# top.net
KiCad netlist of a schematic drawn in Altium Designer
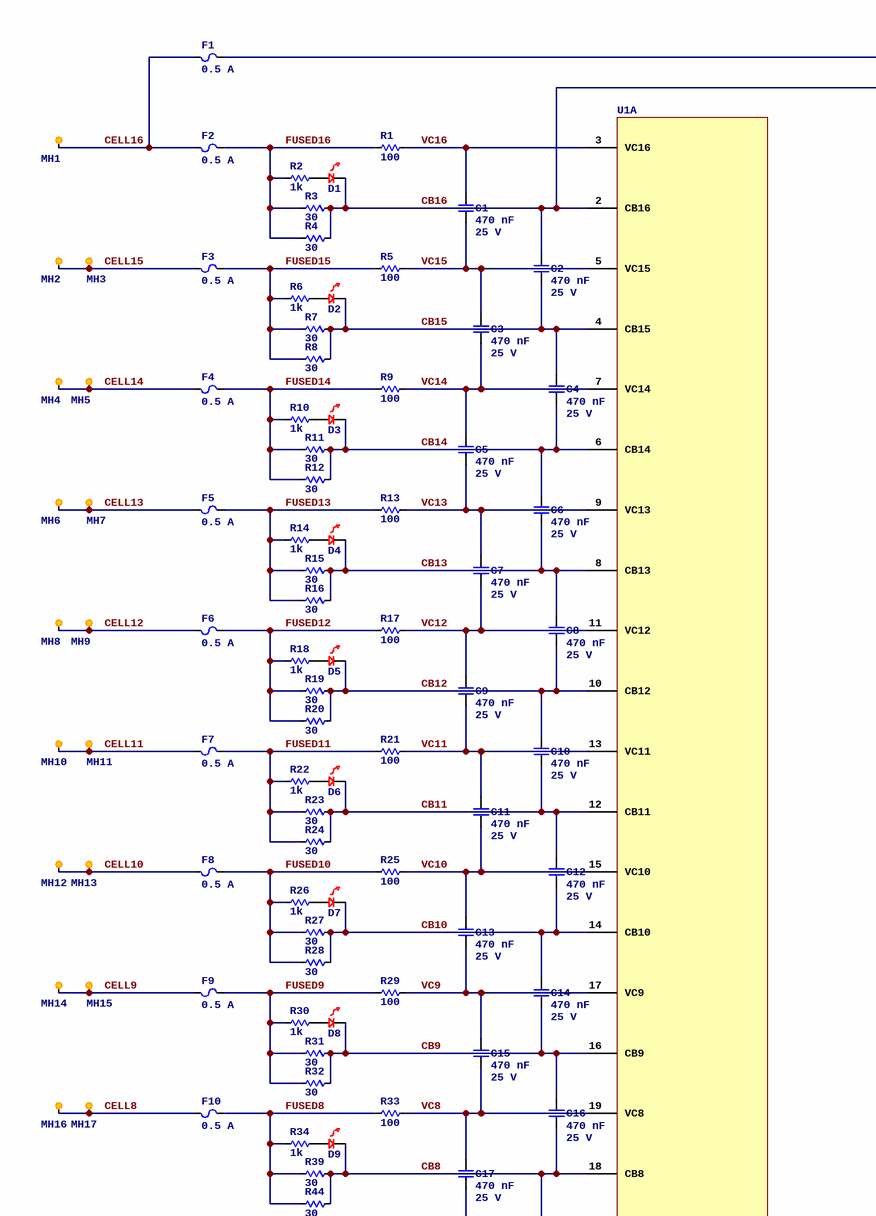
[diagram p0: top.SchDoc, top left]
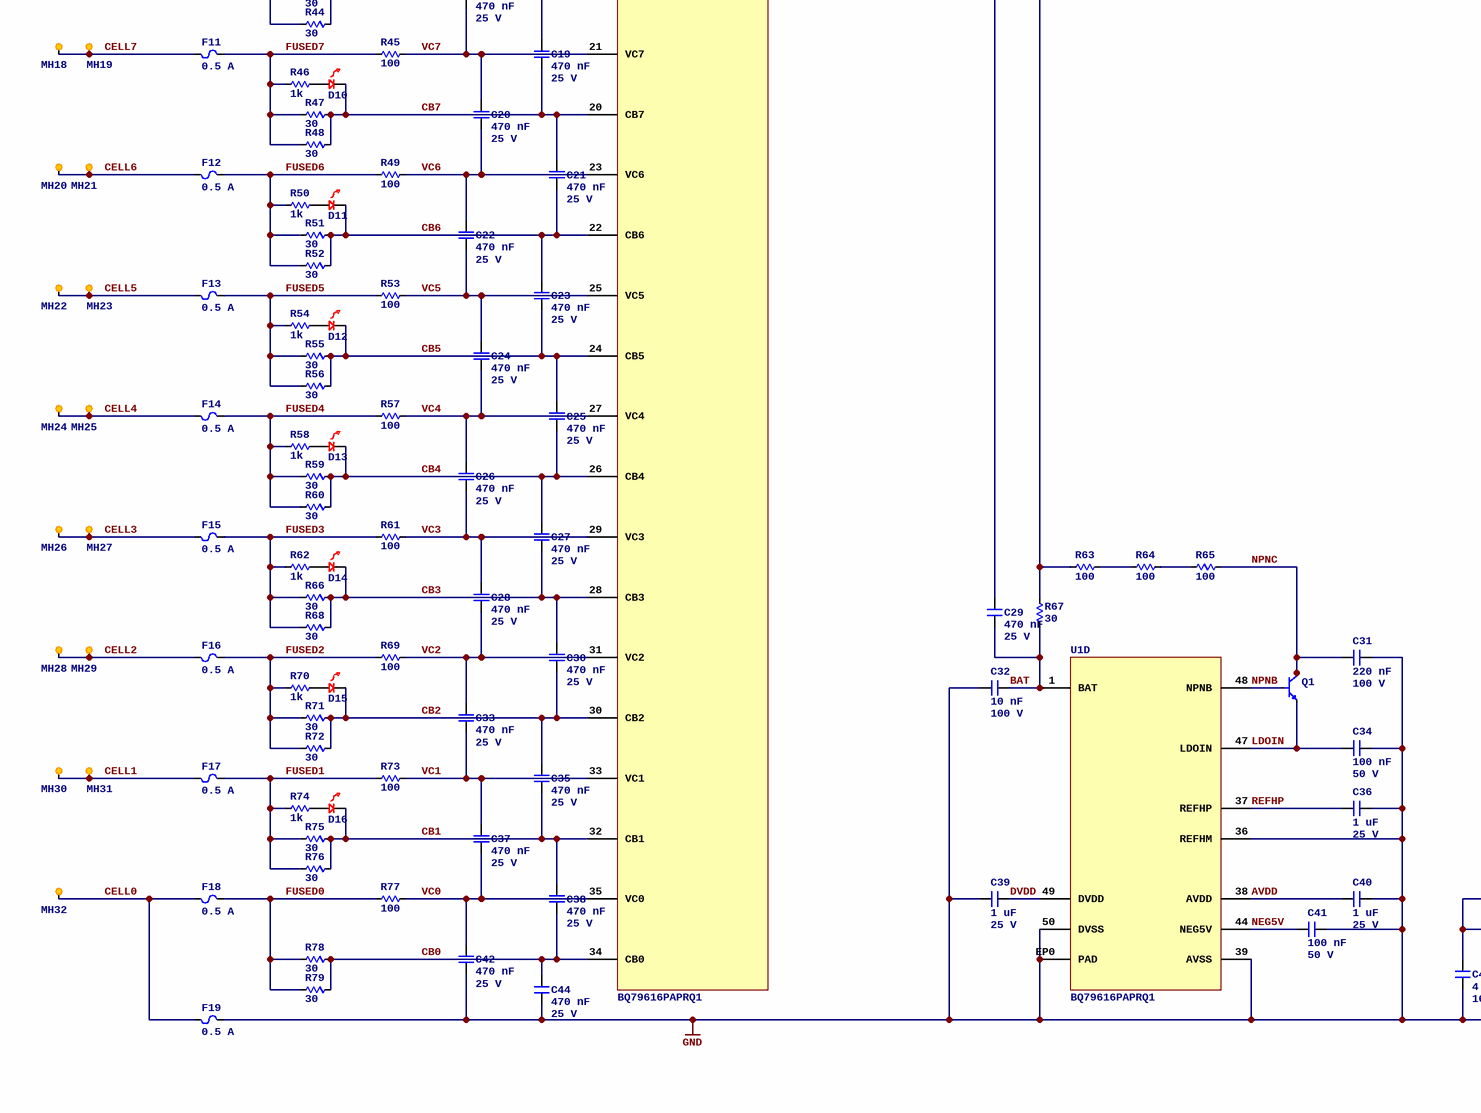
[diagram p1: top.SchDoc, bottom left]
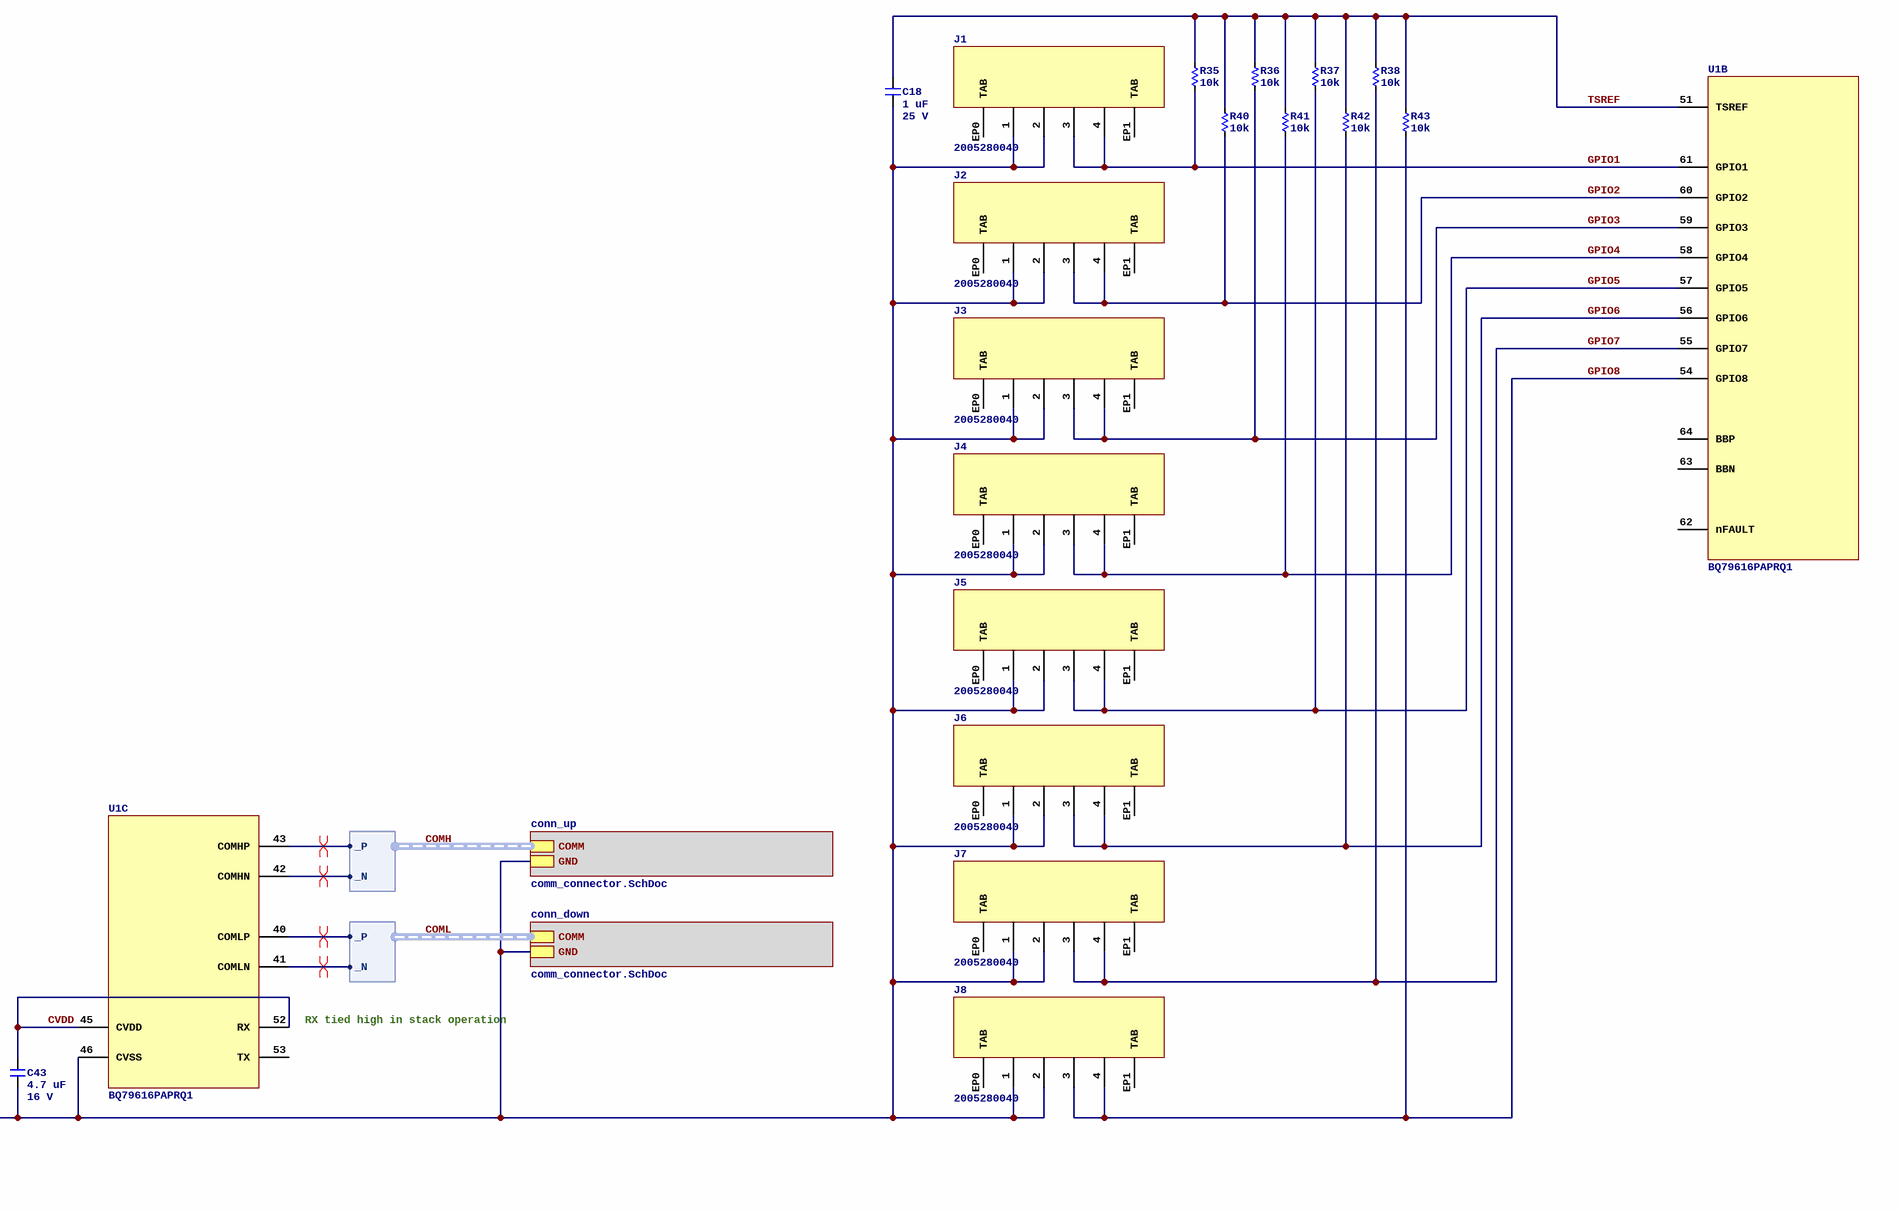
[diagram p2: top.SchDoc, bottom right]

(export (version "E")
  (design (tool "Eeschema 10.0.6"))
  (components
    (comp (ref "C1")
      (value "CL10B474KA8NNNC")
      (footprint "C0603")
      (fields
        (field (name "CAPACITANCE") "470 nF")
        (field (name "MANUFACTURER") "Samsung Electro-Mechanics")
        (field (name "VOLTAGE RATING") "25 V")
      )
      (libsource (lib "database") (part "__template_cap"))
    )
    (comp (ref "C2")
      (value "CL10B474KA8NNNC")
      (footprint "C0603")
      (fields
        (field (name "CAPACITANCE") "470 nF")
        (field (name "MANUFACTURER") "Samsung Electro-Mechanics")
        (field (name "VOLTAGE RATING") "25 V")
      )
      (libsource (lib "database") (part "__template_cap"))
    )
    (comp (ref "C3")
      (value "CL10B474KA8NNNC")
      (footprint "C0603")
      (fields
        (field (name "CAPACITANCE") "470 nF")
        (field (name "MANUFACTURER") "Samsung Electro-Mechanics")
        (field (name "VOLTAGE RATING") "25 V")
      )
      (libsource (lib "database") (part "__template_cap"))
    )
    (comp (ref "C4")
      (value "CL10B474KA8NNNC")
      (footprint "C0603")
      (fields
        (field (name "CAPACITANCE") "470 nF")
        (field (name "MANUFACTURER") "Samsung Electro-Mechanics")
        (field (name "VOLTAGE RATING") "25 V")
      )
      (libsource (lib "database") (part "__template_cap"))
    )
    (comp (ref "C5")
      (value "CL10B474KA8NNNC")
      (footprint "C0603")
      (fields
        (field (name "CAPACITANCE") "470 nF")
        (field (name "MANUFACTURER") "Samsung Electro-Mechanics")
        (field (name "VOLTAGE RATING") "25 V")
      )
      (libsource (lib "database") (part "__template_cap"))
    )
    (comp (ref "C6")
      (value "CL10B474KA8NNNC")
      (footprint "C0603")
      (fields
        (field (name "CAPACITANCE") "470 nF")
        (field (name "MANUFACTURER") "Samsung Electro-Mechanics")
        (field (name "VOLTAGE RATING") "25 V")
      )
      (libsource (lib "database") (part "__template_cap"))
    )
    (comp (ref "C7")
      (value "CL10B474KA8NNNC")
      (footprint "C0603")
      (fields
        (field (name "CAPACITANCE") "470 nF")
        (field (name "MANUFACTURER") "Samsung Electro-Mechanics")
        (field (name "VOLTAGE RATING") "25 V")
      )
      (libsource (lib "database") (part "__template_cap"))
    )
    (comp (ref "C8")
      (value "CL10B474KA8NNNC")
      (footprint "C0603")
      (fields
        (field (name "CAPACITANCE") "470 nF")
        (field (name "MANUFACTURER") "Samsung Electro-Mechanics")
        (field (name "VOLTAGE RATING") "25 V")
      )
      (libsource (lib "database") (part "__template_cap"))
    )
    (comp (ref "C9")
      (value "CL10B474KA8NNNC")
      (footprint "C0603")
      (fields
        (field (name "CAPACITANCE") "470 nF")
        (field (name "MANUFACTURER") "Samsung Electro-Mechanics")
        (field (name "VOLTAGE RATING") "25 V")
      )
      (libsource (lib "database") (part "__template_cap"))
    )
    (comp (ref "C10")
      (value "CL10B474KA8NNNC")
      (footprint "C0603")
      (fields
        (field (name "CAPACITANCE") "470 nF")
        (field (name "MANUFACTURER") "Samsung Electro-Mechanics")
        (field (name "VOLTAGE RATING") "25 V")
      )
      (libsource (lib "database") (part "__template_cap"))
    )
    (comp (ref "C11")
      (value "CL10B474KA8NNNC")
      (footprint "C0603")
      (fields
        (field (name "CAPACITANCE") "470 nF")
        (field (name "MANUFACTURER") "Samsung Electro-Mechanics")
        (field (name "VOLTAGE RATING") "25 V")
      )
      (libsource (lib "database") (part "__template_cap"))
    )
    (comp (ref "C12")
      (value "CL10B474KA8NNNC")
      (footprint "C0603")
      (fields
        (field (name "CAPACITANCE") "470 nF")
        (field (name "MANUFACTURER") "Samsung Electro-Mechanics")
        (field (name "VOLTAGE RATING") "25 V")
      )
      (libsource (lib "database") (part "__template_cap"))
    )
    (comp (ref "C13")
      (value "CL10B474KA8NNNC")
      (footprint "C0603")
      (fields
        (field (name "CAPACITANCE") "470 nF")
        (field (name "MANUFACTURER") "Samsung Electro-Mechanics")
        (field (name "VOLTAGE RATING") "25 V")
      )
      (libsource (lib "database") (part "__template_cap"))
    )
    (comp (ref "C14")
      (value "CL10B474KA8NNNC")
      (footprint "C0603")
      (fields
        (field (name "CAPACITANCE") "470 nF")
        (field (name "MANUFACTURER") "Samsung Electro-Mechanics")
        (field (name "VOLTAGE RATING") "25 V")
      )
      (libsource (lib "database") (part "__template_cap"))
    )
    (comp (ref "C15")
      (value "CL10B474KA8NNNC")
      (footprint "C0603")
      (fields
        (field (name "CAPACITANCE") "470 nF")
        (field (name "MANUFACTURER") "Samsung Electro-Mechanics")
        (field (name "VOLTAGE RATING") "25 V")
      )
      (libsource (lib "database") (part "__template_cap"))
    )
    (comp (ref "C16")
      (value "CL10B474KA8NNNC")
      (footprint "C0603")
      (fields
        (field (name "CAPACITANCE") "470 nF")
        (field (name "MANUFACTURER") "Samsung Electro-Mechanics")
        (field (name "VOLTAGE RATING") "25 V")
      )
      (libsource (lib "database") (part "__template_cap"))
    )
    (comp (ref "C17")
      (value "CL10B474KA8NNNC")
      (footprint "C0603")
      (fields
        (field (name "CAPACITANCE") "470 nF")
        (field (name "MANUFACTURER") "Samsung Electro-Mechanics")
        (field (name "VOLTAGE RATING") "25 V")
      )
      (libsource (lib "database") (part "__template_cap"))
    )
    (comp (ref "C18")
      (value "CL10B105KA8NNNC")
      (footprint "C0603")
      (fields
        (field (name "CAPACITANCE") "1 uF")
        (field (name "MANUFACTURER") "Samsung Electro-Mechanics")
        (field (name "VOLTAGE RATING") "25 V")
      )
      (libsource (lib "database") (part "__template_cap"))
    )
    (comp (ref "C19")
      (value "CL10B474KA8NNNC")
      (footprint "C0603")
      (fields
        (field (name "CAPACITANCE") "470 nF")
        (field (name "MANUFACTURER") "Samsung Electro-Mechanics")
        (field (name "VOLTAGE RATING") "25 V")
      )
      (libsource (lib "database") (part "__template_cap"))
    )
    (comp (ref "C20")
      (value "CL10B474KA8NNNC")
      (footprint "C0603")
      (fields
        (field (name "CAPACITANCE") "470 nF")
        (field (name "MANUFACTURER") "Samsung Electro-Mechanics")
        (field (name "VOLTAGE RATING") "25 V")
      )
      (libsource (lib "database") (part "__template_cap"))
    )
    (comp (ref "C21")
      (value "CL10B474KA8NNNC")
      (footprint "C0603")
      (fields
        (field (name "CAPACITANCE") "470 nF")
        (field (name "MANUFACTURER") "Samsung Electro-Mechanics")
        (field (name "VOLTAGE RATING") "25 V")
      )
      (libsource (lib "database") (part "__template_cap"))
    )
    (comp (ref "C22")
      (value "CL10B474KA8NNNC")
      (footprint "C0603")
      (fields
        (field (name "CAPACITANCE") "470 nF")
        (field (name "MANUFACTURER") "Samsung Electro-Mechanics")
        (field (name "VOLTAGE RATING") "25 V")
      )
      (libsource (lib "database") (part "__template_cap"))
    )
    (comp (ref "C23")
      (value "CL10B474KA8NNNC")
      (footprint "C0603")
      (fields
        (field (name "CAPACITANCE") "470 nF")
        (field (name "MANUFACTURER") "Samsung Electro-Mechanics")
        (field (name "VOLTAGE RATING") "25 V")
      )
      (libsource (lib "database") (part "__template_cap"))
    )
    (comp (ref "C24")
      (value "CL10B474KA8NNNC")
      (footprint "C0603")
      (fields
        (field (name "CAPACITANCE") "470 nF")
        (field (name "MANUFACTURER") "Samsung Electro-Mechanics")
        (field (name "VOLTAGE RATING") "25 V")
      )
      (libsource (lib "database") (part "__template_cap"))
    )
    (comp (ref "C25")
      (value "CL10B474KA8NNNC")
      (footprint "C0603")
      (fields
        (field (name "CAPACITANCE") "470 nF")
        (field (name "MANUFACTURER") "Samsung Electro-Mechanics")
        (field (name "VOLTAGE RATING") "25 V")
      )
      (libsource (lib "database") (part "__template_cap"))
    )
    (comp (ref "C26")
      (value "CL10B474KA8NNNC")
      (footprint "C0603")
      (fields
        (field (name "CAPACITANCE") "470 nF")
        (field (name "MANUFACTURER") "Samsung Electro-Mechanics")
        (field (name "VOLTAGE RATING") "25 V")
      )
      (libsource (lib "database") (part "__template_cap"))
    )
    (comp (ref "C27")
      (value "CL10B474KA8NNNC")
      (footprint "C0603")
      (fields
        (field (name "CAPACITANCE") "470 nF")
        (field (name "MANUFACTURER") "Samsung Electro-Mechanics")
        (field (name "VOLTAGE RATING") "25 V")
      )
      (libsource (lib "database") (part "__template_cap"))
    )
    (comp (ref "C28")
      (value "CL10B474KA8NNNC")
      (footprint "C0603")
      (fields
        (field (name "CAPACITANCE") "470 nF")
        (field (name "MANUFACTURER") "Samsung Electro-Mechanics")
        (field (name "VOLTAGE RATING") "25 V")
      )
      (libsource (lib "database") (part "__template_cap"))
    )
    (comp (ref "C29")
      (value "CL10B474KA8NNNC")
      (footprint "C0603")
      (fields
        (field (name "CAPACITANCE") "470 nF")
        (field (name "MANUFACTURER") "Samsung Electro-Mechanics")
        (field (name "VOLTAGE RATING") "25 V")
      )
      (libsource (lib "database") (part "__template_cap"))
    )
    (comp (ref "C30")
      (value "CL10B474KA8NNNC")
      (footprint "C0603")
      (fields
        (field (name "CAPACITANCE") "470 nF")
        (field (name "MANUFACTURER") "Samsung Electro-Mechanics")
        (field (name "VOLTAGE RATING") "25 V")
      )
      (libsource (lib "database") (part "__template_cap"))
    )
    (comp (ref "C31")
      (value "TCC1206X7R224K101FT")
      (footprint "C1206")
      (fields
        (field (name "CAPACITANCE") "220 nF")
        (field (name "MANUFACTURER") "CCTC")
        (field (name "VOLTAGE RATING") "100 V")
      )
      (libsource (lib "database") (part "__template_cap"))
    )
    (comp (ref "C32")
      (value "CC0402KRX7R0BB103")
      (footprint "C0402")
      (fields
        (field (name "CAPACITANCE") "10 nF")
        (field (name "MANUFACTURER") "YAGEO")
        (field (name "VOLTAGE RATING") "100 V")
      )
      (libsource (lib "database") (part "__template_cap"))
    )
    (comp (ref "C33")
      (value "CL10B474KA8NNNC")
      (footprint "C0603")
      (fields
        (field (name "CAPACITANCE") "470 nF")
        (field (name "MANUFACTURER") "Samsung Electro-Mechanics")
        (field (name "VOLTAGE RATING") "25 V")
      )
      (libsource (lib "database") (part "__template_cap"))
    )
    (comp (ref "C34")
      (value "CL05B104KB54PNC")
      (footprint "C0402")
      (fields
        (field (name "CAPACITANCE") "100 nF")
        (field (name "MANUFACTURER") "Samsung Electro-Mechanics")
        (field (name "VOLTAGE RATING") "50 V")
      )
      (libsource (lib "database") (part "__template_cap"))
    )
    (comp (ref "C35")
      (value "CL10B474KA8NNNC")
      (footprint "C0603")
      (fields
        (field (name "CAPACITANCE") "470 nF")
        (field (name "MANUFACTURER") "Samsung Electro-Mechanics")
        (field (name "VOLTAGE RATING") "25 V")
      )
      (libsource (lib "database") (part "__template_cap"))
    )
    (comp (ref "C36")
      (value "CL10B105KA8NNNC")
      (footprint "C0603")
      (fields
        (field (name "CAPACITANCE") "1 uF")
        (field (name "MANUFACTURER") "Samsung Electro-Mechanics")
        (field (name "VOLTAGE RATING") "25 V")
      )
      (libsource (lib "database") (part "__template_cap"))
    )
    (comp (ref "C37")
      (value "CL10B474KA8NNNC")
      (footprint "C0603")
      (fields
        (field (name "CAPACITANCE") "470 nF")
        (field (name "MANUFACTURER") "Samsung Electro-Mechanics")
        (field (name "VOLTAGE RATING") "25 V")
      )
      (libsource (lib "database") (part "__template_cap"))
    )
    (comp (ref "C38")
      (value "CL10B474KA8NNNC")
      (footprint "C0603")
      (fields
        (field (name "CAPACITANCE") "470 nF")
        (field (name "MANUFACTURER") "Samsung Electro-Mechanics")
        (field (name "VOLTAGE RATING") "25 V")
      )
      (libsource (lib "database") (part "__template_cap"))
    )
    (comp (ref "C39")
      (value "CL10B105KA8NNNC")
      (footprint "C0603")
      (fields
        (field (name "CAPACITANCE") "1 uF")
        (field (name "MANUFACTURER") "Samsung Electro-Mechanics")
        (field (name "VOLTAGE RATING") "25 V")
      )
      (libsource (lib "database") (part "__template_cap"))
    )
    (comp (ref "C40")
      (value "CL10B105KA8NNNC")
      (footprint "C0603")
      (fields
        (field (name "CAPACITANCE") "1 uF")
        (field (name "MANUFACTURER") "Samsung Electro-Mechanics")
        (field (name "VOLTAGE RATING") "25 V")
      )
      (libsource (lib "database") (part "__template_cap"))
    )
    (comp (ref "C41")
      (value "CL05B104KB54PNC")
      (footprint "C0402")
      (fields
        (field (name "CAPACITANCE") "100 nF")
        (field (name "MANUFACTURER") "Samsung Electro-Mechanics")
        (field (name "VOLTAGE RATING") "50 V")
      )
      (libsource (lib "database") (part "__template_cap"))
    )
    (comp (ref "C42")
      (value "CL10B474KA8NNNC")
      (footprint "C0603")
      (fields
        (field (name "CAPACITANCE") "470 nF")
        (field (name "MANUFACTURER") "Samsung Electro-Mechanics")
        (field (name "VOLTAGE RATING") "25 V")
      )
      (libsource (lib "database") (part "__template_cap"))
    )
    (comp (ref "C43")
      (value "CL21B475KOFNNNE")
      (footprint "C0805")
      (fields
        (field (name "CAPACITANCE") "4.7 uF")
        (field (name "MANUFACTURER") "Samsung Electro-Mechanics")
        (field (name "VOLTAGE RATING") "16 V")
      )
      (libsource (lib "database") (part "__template_cap"))
    )
    (comp (ref "C44")
      (value "CL10B474KA8NNNC")
      (footprint "C0603")
      (fields
        (field (name "CAPACITANCE") "470 nF")
        (field (name "MANUFACTURER") "Samsung Electro-Mechanics")
        (field (name "VOLTAGE RATING") "25 V")
      )
      (libsource (lib "database") (part "__template_cap"))
    )
    (comp (ref "D1")
      (value "LTST-C190KRKT")
      (footprint "LED_0603P_RED")
      (description "LED SUPER RED CLEAR 0603 SMD")
      (fields (field (name "MANUFACTURER") "Lite-On Inc"))
      (libsource (lib "database") (part "__template_led_red"))
    )
    (comp (ref "D2")
      (value "LTST-C190KRKT")
      (footprint "LED_0603P_RED")
      (description "LED SUPER RED CLEAR 0603 SMD")
      (fields (field (name "MANUFACTURER") "Lite-On Inc"))
      (libsource (lib "database") (part "__template_led_red"))
    )
    (comp (ref "D3")
      (value "LTST-C190KRKT")
      (footprint "LED_0603P_RED")
      (description "LED SUPER RED CLEAR 0603 SMD")
      (fields (field (name "MANUFACTURER") "Lite-On Inc"))
      (libsource (lib "database") (part "__template_led_red"))
    )
    (comp (ref "D4")
      (value "LTST-C190KRKT")
      (footprint "LED_0603P_RED")
      (description "LED SUPER RED CLEAR 0603 SMD")
      (fields (field (name "MANUFACTURER") "Lite-On Inc"))
      (libsource (lib "database") (part "__template_led_red"))
    )
    (comp (ref "D5")
      (value "LTST-C190KRKT")
      (footprint "LED_0603P_RED")
      (description "LED SUPER RED CLEAR 0603 SMD")
      (fields (field (name "MANUFACTURER") "Lite-On Inc"))
      (libsource (lib "database") (part "__template_led_red"))
    )
    (comp (ref "D6")
      (value "LTST-C190KRKT")
      (footprint "LED_0603P_RED")
      (description "LED SUPER RED CLEAR 0603 SMD")
      (fields (field (name "MANUFACTURER") "Lite-On Inc"))
      (libsource (lib "database") (part "__template_led_red"))
    )
    (comp (ref "D7")
      (value "LTST-C190KRKT")
      (footprint "LED_0603P_RED")
      (description "LED SUPER RED CLEAR 0603 SMD")
      (fields (field (name "MANUFACTURER") "Lite-On Inc"))
      (libsource (lib "database") (part "__template_led_red"))
    )
    (comp (ref "D8")
      (value "LTST-C190KRKT")
      (footprint "LED_0603P_RED")
      (description "LED SUPER RED CLEAR 0603 SMD")
      (fields (field (name "MANUFACTURER") "Lite-On Inc"))
      (libsource (lib "database") (part "__template_led_red"))
    )
    (comp (ref "D9")
      (value "LTST-C190KRKT")
      (footprint "LED_0603P_RED")
      (description "LED SUPER RED CLEAR 0603 SMD")
      (fields (field (name "MANUFACTURER") "Lite-On Inc"))
      (libsource (lib "database") (part "__template_led_red"))
    )
    (comp (ref "D10")
      (value "LTST-C190KRKT")
      (footprint "LED_0603P_RED")
      (description "LED SUPER RED CLEAR 0603 SMD")
      (fields (field (name "MANUFACTURER") "Lite-On Inc"))
      (libsource (lib "database") (part "__template_led_red"))
    )
    (comp (ref "D11")
      (value "LTST-C190KRKT")
      (footprint "LED_0603P_RED")
      (description "LED SUPER RED CLEAR 0603 SMD")
      (fields (field (name "MANUFACTURER") "Lite-On Inc"))
      (libsource (lib "database") (part "__template_led_red"))
    )
    (comp (ref "D12")
      (value "LTST-C190KRKT")
      (footprint "LED_0603P_RED")
      (description "LED SUPER RED CLEAR 0603 SMD")
      (fields (field (name "MANUFACTURER") "Lite-On Inc"))
      (libsource (lib "database") (part "__template_led_red"))
    )
    (comp (ref "D13")
      (value "LTST-C190KRKT")
      (footprint "LED_0603P_RED")
      (description "LED SUPER RED CLEAR 0603 SMD")
      (fields (field (name "MANUFACTURER") "Lite-On Inc"))
      (libsource (lib "database") (part "__template_led_red"))
    )
    (comp (ref "D14")
      (value "LTST-C190KRKT")
      (footprint "LED_0603P_RED")
      (description "LED SUPER RED CLEAR 0603 SMD")
      (fields (field (name "MANUFACTURER") "Lite-On Inc"))
      (libsource (lib "database") (part "__template_led_red"))
    )
    (comp (ref "D15")
      (value "LTST-C190KRKT")
      (footprint "LED_0603P_RED")
      (description "LED SUPER RED CLEAR 0603 SMD")
      (fields (field (name "MANUFACTURER") "Lite-On Inc"))
      (libsource (lib "database") (part "__template_led_red"))
    )
    (comp (ref "D16")
      (value "LTST-C190KRKT")
      (footprint "LED_0603P_RED")
      (description "LED SUPER RED CLEAR 0603 SMD")
      (fields (field (name "MANUFACTURER") "Lite-On Inc"))
      (libsource (lib "database") (part "__template_led_red"))
    )
    (comp (ref "F1")
      (value "JFC2410-0500TS")
      (footprint "JDTFUSE_JFC2410")
      (description "FUSE 0.5A 250V SMD")
      (fields (field (name "MANUFACTURER") "Shenzhen JDTfuse") (field (name "CURRENT") "0.5 A"))
      (libsource (lib "database") (part "JFC2410-0500TS"))
    )
    (comp (ref "F2")
      (value "JFC2410-0500TS")
      (footprint "JDTFUSE_JFC2410")
      (description "FUSE 0.5A 250V SMD")
      (fields (field (name "MANUFACTURER") "Shenzhen JDTfuse") (field (name "CURRENT") "0.5 A"))
      (libsource (lib "database") (part "JFC2410-0500TS"))
    )
    (comp (ref "F3")
      (value "JFC2410-0500TS")
      (footprint "JDTFUSE_JFC2410")
      (description "FUSE 0.5A 250V SMD")
      (fields (field (name "MANUFACTURER") "Shenzhen JDTfuse") (field (name "CURRENT") "0.5 A"))
      (libsource (lib "database") (part "JFC2410-0500TS"))
    )
    (comp (ref "F4")
      (value "JFC2410-0500TS")
      (footprint "JDTFUSE_JFC2410")
      (description "FUSE 0.5A 250V SMD")
      (fields (field (name "MANUFACTURER") "Shenzhen JDTfuse") (field (name "CURRENT") "0.5 A"))
      (libsource (lib "database") (part "JFC2410-0500TS"))
    )
    (comp (ref "F5")
      (value "JFC2410-0500TS")
      (footprint "JDTFUSE_JFC2410")
      (description "FUSE 0.5A 250V SMD")
      (fields (field (name "MANUFACTURER") "Shenzhen JDTfuse") (field (name "CURRENT") "0.5 A"))
      (libsource (lib "database") (part "JFC2410-0500TS"))
    )
    (comp (ref "F6")
      (value "JFC2410-0500TS")
      (footprint "JDTFUSE_JFC2410")
      (description "FUSE 0.5A 250V SMD")
      (fields (field (name "MANUFACTURER") "Shenzhen JDTfuse") (field (name "CURRENT") "0.5 A"))
      (libsource (lib "database") (part "JFC2410-0500TS"))
    )
    (comp (ref "F7")
      (value "JFC2410-0500TS")
      (footprint "JDTFUSE_JFC2410")
      (description "FUSE 0.5A 250V SMD")
      (fields (field (name "MANUFACTURER") "Shenzhen JDTfuse") (field (name "CURRENT") "0.5 A"))
      (libsource (lib "database") (part "JFC2410-0500TS"))
    )
    (comp (ref "F8")
      (value "JFC2410-0500TS")
      (footprint "JDTFUSE_JFC2410")
      (description "FUSE 0.5A 250V SMD")
      (fields (field (name "MANUFACTURER") "Shenzhen JDTfuse") (field (name "CURRENT") "0.5 A"))
      (libsource (lib "database") (part "JFC2410-0500TS"))
    )
    (comp (ref "F9")
      (value "JFC2410-0500TS")
      (footprint "JDTFUSE_JFC2410")
      (description "FUSE 0.5A 250V SMD")
      (fields (field (name "MANUFACTURER") "Shenzhen JDTfuse") (field (name "CURRENT") "0.5 A"))
      (libsource (lib "database") (part "JFC2410-0500TS"))
    )
    (comp (ref "F10")
      (value "JFC2410-0500TS")
      (footprint "JDTFUSE_JFC2410")
      (description "FUSE 0.5A 250V SMD")
      (fields (field (name "MANUFACTURER") "Shenzhen JDTfuse") (field (name "CURRENT") "0.5 A"))
      (libsource (lib "database") (part "JFC2410-0500TS"))
    )
    (comp (ref "F11")
      (value "JFC2410-0500TS")
      (footprint "JDTFUSE_JFC2410")
      (description "FUSE 0.5A 250V SMD")
      (fields (field (name "MANUFACTURER") "Shenzhen JDTfuse") (field (name "CURRENT") "0.5 A"))
      (libsource (lib "database") (part "JFC2410-0500TS"))
    )
    (comp (ref "F12")
      (value "JFC2410-0500TS")
      (footprint "JDTFUSE_JFC2410")
      (description "FUSE 0.5A 250V SMD")
      (fields (field (name "MANUFACTURER") "Shenzhen JDTfuse") (field (name "CURRENT") "0.5 A"))
      (libsource (lib "database") (part "JFC2410-0500TS"))
    )
    (comp (ref "F13")
      (value "JFC2410-0500TS")
      (footprint "JDTFUSE_JFC2410")
      (description "FUSE 0.5A 250V SMD")
      (fields (field (name "MANUFACTURER") "Shenzhen JDTfuse") (field (name "CURRENT") "0.5 A"))
      (libsource (lib "database") (part "JFC2410-0500TS"))
    )
    (comp (ref "F14")
      (value "JFC2410-0500TS")
      (footprint "JDTFUSE_JFC2410")
      (description "FUSE 0.5A 250V SMD")
      (fields (field (name "MANUFACTURER") "Shenzhen JDTfuse") (field (name "CURRENT") "0.5 A"))
      (libsource (lib "database") (part "JFC2410-0500TS"))
    )
    (comp (ref "F15")
      (value "JFC2410-0500TS")
      (footprint "JDTFUSE_JFC2410")
      (description "FUSE 0.5A 250V SMD")
      (fields (field (name "MANUFACTURER") "Shenzhen JDTfuse") (field (name "CURRENT") "0.5 A"))
      (libsource (lib "database") (part "JFC2410-0500TS"))
    )
    (comp (ref "F16")
      (value "JFC2410-0500TS")
      (footprint "JDTFUSE_JFC2410")
      (description "FUSE 0.5A 250V SMD")
      (fields (field (name "MANUFACTURER") "Shenzhen JDTfuse") (field (name "CURRENT") "0.5 A"))
      (libsource (lib "database") (part "JFC2410-0500TS"))
    )
    (comp (ref "F17")
      (value "JFC2410-0500TS")
      (footprint "JDTFUSE_JFC2410")
      (description "FUSE 0.5A 250V SMD")
      (fields (field (name "MANUFACTURER") "Shenzhen JDTfuse") (field (name "CURRENT") "0.5 A"))
      (libsource (lib "database") (part "JFC2410-0500TS"))
    )
    (comp (ref "F18")
      (value "JFC2410-0500TS")
      (footprint "JDTFUSE_JFC2410")
      (description "FUSE 0.5A 250V SMD")
      (fields (field (name "MANUFACTURER") "Shenzhen JDTfuse") (field (name "CURRENT") "0.5 A"))
      (libsource (lib "database") (part "JFC2410-0500TS"))
    )
    (comp (ref "F19")
      (value "JFC2410-0500TS")
      (footprint "JDTFUSE_JFC2410")
      (description "FUSE 0.5A 250V SMD")
      (fields (field (name "MANUFACTURER") "Shenzhen JDTfuse") (field (name "CURRENT") "0.5 A"))
      (libsource (lib "database") (part "JFC2410-0500TS"))
    )
    (comp (ref "J1")
      (value "2005280040")
      (footprint "MOLEX_FD19_1.00mm_2005280040")
      (description "4 Position FFC, FPC Connector Contacts, Bottom 0.039\" (1.00mm) Surface Mount, Right Angle")
      (fields (field (name "MANUFACTURER") "Molex"))
      (libsource (lib "database") (part "2005280040"))
    )
    (comp (ref "J2")
      (value "2005280040")
      (footprint "MOLEX_FD19_1.00mm_2005280040")
      (description "4 Position FFC, FPC Connector Contacts, Bottom 0.039\" (1.00mm) Surface Mount, Right Angle")
      (fields (field (name "MANUFACTURER") "Molex"))
      (libsource (lib "database") (part "2005280040"))
    )
    (comp (ref "J3")
      (value "2005280040")
      (footprint "MOLEX_FD19_1.00mm_2005280040")
      (description "4 Position FFC, FPC Connector Contacts, Bottom 0.039\" (1.00mm) Surface Mount, Right Angle")
      (fields (field (name "MANUFACTURER") "Molex"))
      (libsource (lib "database") (part "2005280040"))
    )
    (comp (ref "J4")
      (value "2005280040")
      (footprint "MOLEX_FD19_1.00mm_2005280040")
      (description "4 Position FFC, FPC Connector Contacts, Bottom 0.039\" (1.00mm) Surface Mount, Right Angle")
      (fields (field (name "MANUFACTURER") "Molex"))
      (libsource (lib "database") (part "2005280040"))
    )
    (comp (ref "J5")
      (value "2005280040")
      (footprint "MOLEX_FD19_1.00mm_2005280040")
      (description "4 Position FFC, FPC Connector Contacts, Bottom 0.039\" (1.00mm) Surface Mount, Right Angle")
      (fields (field (name "MANUFACTURER") "Molex"))
      (libsource (lib "database") (part "2005280040"))
    )
    (comp (ref "J6")
      (value "2005280040")
      (footprint "MOLEX_FD19_1.00mm_2005280040")
      (description "4 Position FFC, FPC Connector Contacts, Bottom 0.039\" (1.00mm) Surface Mount, Right Angle")
      (fields (field (name "MANUFACTURER") "Molex"))
      (libsource (lib "database") (part "2005280040"))
    )
    (comp (ref "J7")
      (value "2005280040")
      (footprint "MOLEX_FD19_1.00mm_2005280040")
      (description "4 Position FFC, FPC Connector Contacts, Bottom 0.039\" (1.00mm) Surface Mount, Right Angle")
      (fields (field (name "MANUFACTURER") "Molex"))
      (libsource (lib "database") (part "2005280040"))
    )
    (comp (ref "J8")
      (value "2005280040")
      (footprint "MOLEX_FD19_1.00mm_2005280040")
      (description "4 Position FFC, FPC Connector Contacts, Bottom 0.039\" (1.00mm) Surface Mount, Right Angle")
      (fields (field (name "MANUFACTURER") "Molex"))
      (libsource (lib "database") (part "2005280040"))
    )
    (comp (ref "MH1") (value "HOLE_M2") (footprint "HOLE_M2") (libsource (lib "database") (part "HOLE")))
    (comp (ref "MH2") (value "HOLE_M2") (footprint "HOLE_M2") (libsource (lib "database") (part "HOLE")))
    (comp (ref "MH3") (value "HOLE_M2") (footprint "HOLE_M2") (libsource (lib "database") (part "HOLE")))
    (comp (ref "MH4") (value "HOLE_M2") (footprint "HOLE_M2") (libsource (lib "database") (part "HOLE")))
    (comp (ref "MH5") (value "HOLE_M2") (footprint "HOLE_M2") (libsource (lib "database") (part "HOLE")))
    (comp (ref "MH6") (value "HOLE_M2") (footprint "HOLE_M2") (libsource (lib "database") (part "HOLE")))
    (comp (ref "MH7") (value "HOLE_M2") (footprint "HOLE_M2") (libsource (lib "database") (part "HOLE")))
    (comp (ref "MH8") (value "HOLE_M2") (footprint "HOLE_M2") (libsource (lib "database") (part "HOLE")))
    (comp (ref "MH9") (value "HOLE_M2") (footprint "HOLE_M2") (libsource (lib "database") (part "HOLE")))
    (comp (ref "MH10") (value "HOLE_M2") (footprint "HOLE_M2") (libsource (lib "database") (part "HOLE")))
    (comp (ref "MH11") (value "HOLE_M2") (footprint "HOLE_M2") (libsource (lib "database") (part "HOLE")))
    (comp (ref "MH12") (value "HOLE_M2") (footprint "HOLE_M2") (libsource (lib "database") (part "HOLE")))
    (comp (ref "MH13") (value "HOLE_M2") (footprint "HOLE_M2") (libsource (lib "database") (part "HOLE")))
    (comp (ref "MH14") (value "HOLE_M2") (footprint "HOLE_M2") (libsource (lib "database") (part "HOLE")))
    (comp (ref "MH15") (value "HOLE_M2") (footprint "HOLE_M2") (libsource (lib "database") (part "HOLE")))
    (comp (ref "MH16") (value "HOLE_M2") (footprint "HOLE_M2") (libsource (lib "database") (part "HOLE")))
    (comp (ref "MH17") (value "HOLE_M2") (footprint "HOLE_M2") (libsource (lib "database") (part "HOLE")))
    (comp (ref "MH18") (value "HOLE_M2") (footprint "HOLE_M2") (libsource (lib "database") (part "HOLE")))
    (comp (ref "MH19") (value "HOLE_M2") (footprint "HOLE_M2") (libsource (lib "database") (part "HOLE")))
    (comp (ref "MH20") (value "HOLE_M2") (footprint "HOLE_M2") (libsource (lib "database") (part "HOLE")))
    (comp (ref "MH21") (value "HOLE_M2") (footprint "HOLE_M2") (libsource (lib "database") (part "HOLE")))
    (comp (ref "MH22") (value "HOLE_M2") (footprint "HOLE_M2") (libsource (lib "database") (part "HOLE")))
    (comp (ref "MH23") (value "HOLE_M2") (footprint "HOLE_M2") (libsource (lib "database") (part "HOLE")))
    (comp (ref "MH24") (value "HOLE_M2") (footprint "HOLE_M2") (libsource (lib "database") (part "HOLE")))
    (comp (ref "MH25") (value "HOLE_M2") (footprint "HOLE_M2") (libsource (lib "database") (part "HOLE")))
    (comp (ref "MH26") (value "HOLE_M2") (footprint "HOLE_M2") (libsource (lib "database") (part "HOLE")))
    (comp (ref "MH27") (value "HOLE_M2") (footprint "HOLE_M2") (libsource (lib "database") (part "HOLE")))
    (comp (ref "MH28") (value "HOLE_M2") (footprint "HOLE_M2") (libsource (lib "database") (part "HOLE")))
    (comp (ref "MH29") (value "HOLE_M2") (footprint "HOLE_M2") (libsource (lib "database") (part "HOLE")))
    (comp (ref "MH30") (value "HOLE_M2") (footprint "HOLE_M2") (libsource (lib "database") (part "HOLE")))
    (comp (ref "MH31") (value "HOLE_M2") (footprint "HOLE_M2") (libsource (lib "database") (part "HOLE")))
    (comp (ref "MH32") (value "HOLE_M2") (footprint "HOLE_M2") (libsource (lib "database") (part "HOLE")))
    (comp (ref "Q1")
      (value "NSV1C201MZ4T1G")
      (footprint "4SOT223")
      (description "Small Signal Bipolar Transistor, 2A I(C), 100V V(BR)CEO, 1-Element, NPN, Silicon, TO-261AA")
      (fields (field (name "MANUFACTURER") "ON Semiconductor") (field (name "VOLTAGE") "100 V"))
      (libsource (lib "database") (part "NSV1C201MZ4T1G"))
    )
    (comp (ref "R1")
      (value "100")
      (footprint "R0402")
      (fields
        (field (name "MANUFACTURER PART NUMBER") "RC0402FR-07100RL")
        (field (name "MANUFACTURER") "YAGEO")
        (field (name "TOLERANCE") "1%")
      )
      (libsource (lib "database") (part "__template_resistor"))
    )
    (comp (ref "R2")
      (value "1k")
      (footprint "R0402")
      (fields
        (field (name "TOLERANCE") "1%")
        (field (name "MANUFACTURER PART NUMBER") "0402WGF1001TCE")
        (field (name "MANUFACTURER") "UNI-ROYAL(Uniroyal Elec)")
      )
      (libsource (lib "database") (part "__template_resistor"))
    )
    (comp (ref "R3")
      (value "30")
      (footprint "R2512")
      (fields
        (field (name "MANUFACTURER PART NUMBER") "RC2512FK-0730RL")
        (field (name "MANUFACTURER") "YAGEO")
        (field (name "TOLERANCE") "1%")
      )
      (libsource (lib "database") (part "__template_resistor"))
    )
    (comp (ref "R4")
      (value "30")
      (footprint "R2512")
      (fields
        (field (name "MANUFACTURER PART NUMBER") "RC2512FK-0730RL")
        (field (name "MANUFACTURER") "YAGEO")
        (field (name "TOLERANCE") "1%")
      )
      (libsource (lib "database") (part "__template_resistor"))
    )
    (comp (ref "R5")
      (value "100")
      (footprint "R0402")
      (fields
        (field (name "MANUFACTURER PART NUMBER") "RC0402FR-07100RL")
        (field (name "MANUFACTURER") "YAGEO")
        (field (name "TOLERANCE") "1%")
      )
      (libsource (lib "database") (part "__template_resistor"))
    )
    (comp (ref "R6")
      (value "1k")
      (footprint "R0402")
      (fields
        (field (name "TOLERANCE") "1%")
        (field (name "MANUFACTURER PART NUMBER") "0402WGF1001TCE")
        (field (name "MANUFACTURER") "UNI-ROYAL(Uniroyal Elec)")
      )
      (libsource (lib "database") (part "__template_resistor"))
    )
    (comp (ref "R7")
      (value "30")
      (footprint "R2512")
      (fields
        (field (name "MANUFACTURER PART NUMBER") "RC2512FK-0730RL")
        (field (name "MANUFACTURER") "YAGEO")
        (field (name "TOLERANCE") "1%")
      )
      (libsource (lib "database") (part "__template_resistor"))
    )
    (comp (ref "R8")
      (value "30")
      (footprint "R2512")
      (fields
        (field (name "MANUFACTURER PART NUMBER") "RC2512FK-0730RL")
        (field (name "MANUFACTURER") "YAGEO")
        (field (name "TOLERANCE") "1%")
      )
      (libsource (lib "database") (part "__template_resistor"))
    )
    (comp (ref "R9")
      (value "100")
      (footprint "R0402")
      (fields
        (field (name "MANUFACTURER PART NUMBER") "RC0402FR-07100RL")
        (field (name "MANUFACTURER") "YAGEO")
        (field (name "TOLERANCE") "1%")
      )
      (libsource (lib "database") (part "__template_resistor"))
    )
    (comp (ref "R10")
      (value "1k")
      (footprint "R0402")
      (fields
        (field (name "TOLERANCE") "1%")
        (field (name "MANUFACTURER PART NUMBER") "0402WGF1001TCE")
        (field (name "MANUFACTURER") "UNI-ROYAL(Uniroyal Elec)")
      )
      (libsource (lib "database") (part "__template_resistor"))
    )
    (comp (ref "R11")
      (value "30")
      (footprint "R2512")
      (fields
        (field (name "MANUFACTURER PART NUMBER") "RC2512FK-0730RL")
        (field (name "MANUFACTURER") "YAGEO")
        (field (name "TOLERANCE") "1%")
      )
      (libsource (lib "database") (part "__template_resistor"))
    )
    (comp (ref "R12")
      (value "30")
      (footprint "R2512")
      (fields
        (field (name "MANUFACTURER PART NUMBER") "RC2512FK-0730RL")
        (field (name "MANUFACTURER") "YAGEO")
        (field (name "TOLERANCE") "1%")
      )
      (libsource (lib "database") (part "__template_resistor"))
    )
    (comp (ref "R13")
      (value "100")
      (footprint "R0402")
      (fields
        (field (name "MANUFACTURER PART NUMBER") "RC0402FR-07100RL")
        (field (name "MANUFACTURER") "YAGEO")
        (field (name "TOLERANCE") "1%")
      )
      (libsource (lib "database") (part "__template_resistor"))
    )
    (comp (ref "R14")
      (value "1k")
      (footprint "R0402")
      (fields
        (field (name "TOLERANCE") "1%")
        (field (name "MANUFACTURER PART NUMBER") "0402WGF1001TCE")
        (field (name "MANUFACTURER") "UNI-ROYAL(Uniroyal Elec)")
      )
      (libsource (lib "database") (part "__template_resistor"))
    )
    (comp (ref "R15")
      (value "30")
      (footprint "R2512")
      (fields
        (field (name "MANUFACTURER PART NUMBER") "RC2512FK-0730RL")
        (field (name "MANUFACTURER") "YAGEO")
        (field (name "TOLERANCE") "1%")
      )
      (libsource (lib "database") (part "__template_resistor"))
    )
    (comp (ref "R16")
      (value "30")
      (footprint "R2512")
      (fields
        (field (name "MANUFACTURER PART NUMBER") "RC2512FK-0730RL")
        (field (name "MANUFACTURER") "YAGEO")
        (field (name "TOLERANCE") "1%")
      )
      (libsource (lib "database") (part "__template_resistor"))
    )
    (comp (ref "R17")
      (value "100")
      (footprint "R0402")
      (fields
        (field (name "MANUFACTURER PART NUMBER") "RC0402FR-07100RL")
        (field (name "MANUFACTURER") "YAGEO")
        (field (name "TOLERANCE") "1%")
      )
      (libsource (lib "database") (part "__template_resistor"))
    )
    (comp (ref "R18")
      (value "1k")
      (footprint "R0402")
      (fields
        (field (name "TOLERANCE") "1%")
        (field (name "MANUFACTURER PART NUMBER") "0402WGF1001TCE")
        (field (name "MANUFACTURER") "UNI-ROYAL(Uniroyal Elec)")
      )
      (libsource (lib "database") (part "__template_resistor"))
    )
    (comp (ref "R19")
      (value "30")
      (footprint "R2512")
      (fields
        (field (name "MANUFACTURER PART NUMBER") "RC2512FK-0730RL")
        (field (name "MANUFACTURER") "YAGEO")
        (field (name "TOLERANCE") "1%")
      )
      (libsource (lib "database") (part "__template_resistor"))
    )
    (comp (ref "R20")
      (value "30")
      (footprint "R2512")
      (fields
        (field (name "MANUFACTURER PART NUMBER") "RC2512FK-0730RL")
        (field (name "MANUFACTURER") "YAGEO")
        (field (name "TOLERANCE") "1%")
      )
      (libsource (lib "database") (part "__template_resistor"))
    )
    (comp (ref "R21")
      (value "100")
      (footprint "R0402")
      (fields
        (field (name "MANUFACTURER PART NUMBER") "RC0402FR-07100RL")
        (field (name "MANUFACTURER") "YAGEO")
        (field (name "TOLERANCE") "1%")
      )
      (libsource (lib "database") (part "__template_resistor"))
    )
    (comp (ref "R22")
      (value "1k")
      (footprint "R0402")
      (fields
        (field (name "TOLERANCE") "1%")
        (field (name "MANUFACTURER PART NUMBER") "0402WGF1001TCE")
        (field (name "MANUFACTURER") "UNI-ROYAL(Uniroyal Elec)")
      )
      (libsource (lib "database") (part "__template_resistor"))
    )
    (comp (ref "R23")
      (value "30")
      (footprint "R2512")
      (fields
        (field (name "MANUFACTURER PART NUMBER") "RC2512FK-0730RL")
        (field (name "MANUFACTURER") "YAGEO")
        (field (name "TOLERANCE") "1%")
      )
      (libsource (lib "database") (part "__template_resistor"))
    )
    (comp (ref "R24")
      (value "30")
      (footprint "R2512")
      (fields
        (field (name "MANUFACTURER PART NUMBER") "RC2512FK-0730RL")
        (field (name "MANUFACTURER") "YAGEO")
        (field (name "TOLERANCE") "1%")
      )
      (libsource (lib "database") (part "__template_resistor"))
    )
    (comp (ref "R25")
      (value "100")
      (footprint "R0402")
      (fields
        (field (name "MANUFACTURER PART NUMBER") "RC0402FR-07100RL")
        (field (name "MANUFACTURER") "YAGEO")
        (field (name "TOLERANCE") "1%")
      )
      (libsource (lib "database") (part "__template_resistor"))
    )
    (comp (ref "R26")
      (value "1k")
      (footprint "R0402")
      (fields
        (field (name "TOLERANCE") "1%")
        (field (name "MANUFACTURER PART NUMBER") "0402WGF1001TCE")
        (field (name "MANUFACTURER") "UNI-ROYAL(Uniroyal Elec)")
      )
      (libsource (lib "database") (part "__template_resistor"))
    )
    (comp (ref "R27")
      (value "30")
      (footprint "R2512")
      (fields
        (field (name "MANUFACTURER PART NUMBER") "RC2512FK-0730RL")
        (field (name "MANUFACTURER") "YAGEO")
        (field (name "TOLERANCE") "1%")
      )
      (libsource (lib "database") (part "__template_resistor"))
    )
    (comp (ref "R28")
      (value "30")
      (footprint "R2512")
      (fields
        (field (name "MANUFACTURER PART NUMBER") "RC2512FK-0730RL")
        (field (name "MANUFACTURER") "YAGEO")
        (field (name "TOLERANCE") "1%")
      )
      (libsource (lib "database") (part "__template_resistor"))
    )
    (comp (ref "R29")
      (value "100")
      (footprint "R0402")
      (fields
        (field (name "MANUFACTURER PART NUMBER") "RC0402FR-07100RL")
        (field (name "MANUFACTURER") "YAGEO")
        (field (name "TOLERANCE") "1%")
      )
      (libsource (lib "database") (part "__template_resistor"))
    )
    (comp (ref "R30")
      (value "1k")
      (footprint "R0402")
      (fields
        (field (name "TOLERANCE") "1%")
        (field (name "MANUFACTURER PART NUMBER") "0402WGF1001TCE")
        (field (name "MANUFACTURER") "UNI-ROYAL(Uniroyal Elec)")
      )
      (libsource (lib "database") (part "__template_resistor"))
    )
    (comp (ref "R31")
      (value "30")
      (footprint "R2512")
      (fields
        (field (name "MANUFACTURER PART NUMBER") "RC2512FK-0730RL")
        (field (name "MANUFACTURER") "YAGEO")
        (field (name "TOLERANCE") "1%")
      )
      (libsource (lib "database") (part "__template_resistor"))
    )
    (comp (ref "R32")
      (value "30")
      (footprint "R2512")
      (fields
        (field (name "MANUFACTURER PART NUMBER") "RC2512FK-0730RL")
        (field (name "MANUFACTURER") "YAGEO")
        (field (name "TOLERANCE") "1%")
      )
      (libsource (lib "database") (part "__template_resistor"))
    )
    (comp (ref "R33")
      (value "100")
      (footprint "R0402")
      (fields
        (field (name "MANUFACTURER PART NUMBER") "RC0402FR-07100RL")
        (field (name "MANUFACTURER") "YAGEO")
        (field (name "TOLERANCE") "1%")
      )
      (libsource (lib "database") (part "__template_resistor"))
    )
    (comp (ref "R34")
      (value "1k")
      (footprint "R0402")
      (fields
        (field (name "TOLERANCE") "1%")
        (field (name "MANUFACTURER PART NUMBER") "0402WGF1001TCE")
        (field (name "MANUFACTURER") "UNI-ROYAL(Uniroyal Elec)")
      )
      (libsource (lib "database") (part "__template_resistor"))
    )
    (comp (ref "R35")
      (value "10k")
      (footprint "R0402")
      (fields
        (field (name "TOLERANCE") "1%")
        (field (name "MANUFACTURER PART NUMBER") "0402WGF1002TCE")
        (field (name "MANUFACTURER") "UNI-ROYAL(Uniroyal Elec)")
      )
      (libsource (lib "database") (part "__template_resistor"))
    )
    (comp (ref "R36")
      (value "10k")
      (footprint "R0402")
      (fields
        (field (name "TOLERANCE") "1%")
        (field (name "MANUFACTURER PART NUMBER") "0402WGF1002TCE")
        (field (name "MANUFACTURER") "UNI-ROYAL(Uniroyal Elec)")
      )
      (libsource (lib "database") (part "__template_resistor"))
    )
    (comp (ref "R37")
      (value "10k")
      (footprint "R0402")
      (fields
        (field (name "TOLERANCE") "1%")
        (field (name "MANUFACTURER PART NUMBER") "0402WGF1002TCE")
        (field (name "MANUFACTURER") "UNI-ROYAL(Uniroyal Elec)")
      )
      (libsource (lib "database") (part "__template_resistor"))
    )
    (comp (ref "R38")
      (value "10k")
      (footprint "R0402")
      (fields
        (field (name "TOLERANCE") "1%")
        (field (name "MANUFACTURER PART NUMBER") "0402WGF1002TCE")
        (field (name "MANUFACTURER") "UNI-ROYAL(Uniroyal Elec)")
      )
      (libsource (lib "database") (part "__template_resistor"))
    )
    (comp (ref "R39")
      (value "30")
      (footprint "R2512")
      (fields
        (field (name "MANUFACTURER PART NUMBER") "RC2512FK-0730RL")
        (field (name "MANUFACTURER") "YAGEO")
        (field (name "TOLERANCE") "1%")
      )
      (libsource (lib "database") (part "__template_resistor"))
    )
    (comp (ref "R40")
      (value "10k")
      (footprint "R0402")
      (fields
        (field (name "TOLERANCE") "1%")
        (field (name "MANUFACTURER PART NUMBER") "0402WGF1002TCE")
        (field (name "MANUFACTURER") "UNI-ROYAL(Uniroyal Elec)")
      )
      (libsource (lib "database") (part "__template_resistor"))
    )
    (comp (ref "R41")
      (value "10k")
      (footprint "R0402")
      (fields
        (field (name "TOLERANCE") "1%")
        (field (name "MANUFACTURER PART NUMBER") "0402WGF1002TCE")
        (field (name "MANUFACTURER") "UNI-ROYAL(Uniroyal Elec)")
      )
      (libsource (lib "database") (part "__template_resistor"))
    )
    (comp (ref "R42")
      (value "10k")
      (footprint "R0402")
      (fields
        (field (name "TOLERANCE") "1%")
        (field (name "MANUFACTURER PART NUMBER") "0402WGF1002TCE")
        (field (name "MANUFACTURER") "UNI-ROYAL(Uniroyal Elec)")
      )
      (libsource (lib "database") (part "__template_resistor"))
    )
    (comp (ref "R43")
      (value "10k")
      (footprint "R0402")
      (fields
        (field (name "TOLERANCE") "1%")
        (field (name "MANUFACTURER PART NUMBER") "0402WGF1002TCE")
        (field (name "MANUFACTURER") "UNI-ROYAL(Uniroyal Elec)")
      )
      (libsource (lib "database") (part "__template_resistor"))
    )
    (comp (ref "R44")
      (value "30")
      (footprint "R2512")
      (fields
        (field (name "MANUFACTURER PART NUMBER") "RC2512FK-0730RL")
        (field (name "MANUFACTURER") "YAGEO")
        (field (name "TOLERANCE") "1%")
      )
      (libsource (lib "database") (part "__template_resistor"))
    )
    (comp (ref "R45")
      (value "100")
      (footprint "R0402")
      (fields
        (field (name "MANUFACTURER PART NUMBER") "RC0402FR-07100RL")
        (field (name "MANUFACTURER") "YAGEO")
        (field (name "TOLERANCE") "1%")
      )
      (libsource (lib "database") (part "__template_resistor"))
    )
    (comp (ref "R46")
      (value "1k")
      (footprint "R0402")
      (fields
        (field (name "TOLERANCE") "1%")
        (field (name "MANUFACTURER PART NUMBER") "0402WGF1001TCE")
        (field (name "MANUFACTURER") "UNI-ROYAL(Uniroyal Elec)")
      )
      (libsource (lib "database") (part "__template_resistor"))
    )
    (comp (ref "R47")
      (value "30")
      (footprint "R2512")
      (fields
        (field (name "MANUFACTURER PART NUMBER") "RC2512FK-0730RL")
        (field (name "MANUFACTURER") "YAGEO")
        (field (name "TOLERANCE") "1%")
      )
      (libsource (lib "database") (part "__template_resistor"))
    )
    (comp (ref "R48")
      (value "30")
      (footprint "R2512")
      (fields
        (field (name "MANUFACTURER PART NUMBER") "RC2512FK-0730RL")
        (field (name "MANUFACTURER") "YAGEO")
        (field (name "TOLERANCE") "1%")
      )
      (libsource (lib "database") (part "__template_resistor"))
    )
    (comp (ref "R49")
      (value "100")
      (footprint "R0402")
      (fields
        (field (name "MANUFACTURER PART NUMBER") "RC0402FR-07100RL")
        (field (name "MANUFACTURER") "YAGEO")
        (field (name "TOLERANCE") "1%")
      )
      (libsource (lib "database") (part "__template_resistor"))
    )
    (comp (ref "R50")
      (value "1k")
      (footprint "R0402")
      (fields
        (field (name "TOLERANCE") "1%")
        (field (name "MANUFACTURER PART NUMBER") "0402WGF1001TCE")
        (field (name "MANUFACTURER") "UNI-ROYAL(Uniroyal Elec)")
      )
      (libsource (lib "database") (part "__template_resistor"))
    )
    (comp (ref "R51")
      (value "30")
      (footprint "R2512")
      (fields
        (field (name "MANUFACTURER PART NUMBER") "RC2512FK-0730RL")
        (field (name "MANUFACTURER") "YAGEO")
        (field (name "TOLERANCE") "1%")
      )
      (libsource (lib "database") (part "__template_resistor"))
    )
    (comp (ref "R52")
      (value "30")
      (footprint "R2512")
      (fields
        (field (name "MANUFACTURER PART NUMBER") "RC2512FK-0730RL")
        (field (name "MANUFACTURER") "YAGEO")
        (field (name "TOLERANCE") "1%")
      )
      (libsource (lib "database") (part "__template_resistor"))
    )
    (comp (ref "R53")
      (value "100")
      (footprint "R0402")
      (fields
        (field (name "MANUFACTURER PART NUMBER") "RC0402FR-07100RL")
        (field (name "MANUFACTURER") "YAGEO")
        (field (name "TOLERANCE") "1%")
      )
      (libsource (lib "database") (part "__template_resistor"))
    )
    (comp (ref "R54")
      (value "1k")
      (footprint "R0402")
      (fields
        (field (name "TOLERANCE") "1%")
        (field (name "MANUFACTURER PART NUMBER") "0402WGF1001TCE")
        (field (name "MANUFACTURER") "UNI-ROYAL(Uniroyal Elec)")
      )
      (libsource (lib "database") (part "__template_resistor"))
    )
    (comp (ref "R55")
      (value "30")
      (footprint "R2512")
      (fields
        (field (name "MANUFACTURER PART NUMBER") "RC2512FK-0730RL")
        (field (name "MANUFACTURER") "YAGEO")
        (field (name "TOLERANCE") "1%")
      )
      (libsource (lib "database") (part "__template_resistor"))
    )
    (comp (ref "R56")
      (value "30")
      (footprint "R2512")
      (fields
        (field (name "MANUFACTURER PART NUMBER") "RC2512FK-0730RL")
        (field (name "MANUFACTURER") "YAGEO")
        (field (name "TOLERANCE") "1%")
      )
      (libsource (lib "database") (part "__template_resistor"))
    )
    (comp (ref "R57")
      (value "100")
      (footprint "R0402")
      (fields
        (field (name "MANUFACTURER PART NUMBER") "RC0402FR-07100RL")
        (field (name "MANUFACTURER") "YAGEO")
        (field (name "TOLERANCE") "1%")
      )
      (libsource (lib "database") (part "__template_resistor"))
    )
    (comp (ref "R58")
      (value "1k")
      (footprint "R0402")
      (fields
        (field (name "TOLERANCE") "1%")
        (field (name "MANUFACTURER PART NUMBER") "0402WGF1001TCE")
        (field (name "MANUFACTURER") "UNI-ROYAL(Uniroyal Elec)")
      )
      (libsource (lib "database") (part "__template_resistor"))
    )
    (comp (ref "R59")
      (value "30")
      (footprint "R2512")
      (fields
        (field (name "MANUFACTURER PART NUMBER") "RC2512FK-0730RL")
        (field (name "MANUFACTURER") "YAGEO")
        (field (name "TOLERANCE") "1%")
      )
      (libsource (lib "database") (part "__template_resistor"))
    )
    (comp (ref "R60")
      (value "30")
      (footprint "R2512")
      (fields
        (field (name "MANUFACTURER PART NUMBER") "RC2512FK-0730RL")
        (field (name "MANUFACTURER") "YAGEO")
        (field (name "TOLERANCE") "1%")
      )
      (libsource (lib "database") (part "__template_resistor"))
    )
    (comp (ref "R61")
      (value "100")
      (footprint "R0402")
      (fields
        (field (name "MANUFACTURER PART NUMBER") "RC0402FR-07100RL")
        (field (name "MANUFACTURER") "YAGEO")
        (field (name "TOLERANCE") "1%")
      )
      (libsource (lib "database") (part "__template_resistor"))
    )
    (comp (ref "R62")
      (value "1k")
      (footprint "R0402")
      (fields
        (field (name "TOLERANCE") "1%")
        (field (name "MANUFACTURER PART NUMBER") "0402WGF1001TCE")
        (field (name "MANUFACTURER") "UNI-ROYAL(Uniroyal Elec)")
      )
      (libsource (lib "database") (part "__template_resistor"))
    )
    (comp (ref "R63")
      (value "100")
      (footprint "R0402")
      (fields
        (field (name "MANUFACTURER PART NUMBER") "RC0402FR-07100RL")
        (field (name "MANUFACTURER") "YAGEO")
        (field (name "TOLERANCE") "1%")
      )
      (libsource (lib "database") (part "__template_resistor"))
    )
    (comp (ref "R64")
      (value "100")
      (footprint "R0402")
      (fields
        (field (name "MANUFACTURER PART NUMBER") "RC0402FR-07100RL")
        (field (name "MANUFACTURER") "YAGEO")
        (field (name "TOLERANCE") "1%")
      )
      (libsource (lib "database") (part "__template_resistor"))
    )
    (comp (ref "R65")
      (value "100")
      (footprint "R0402")
      (fields
        (field (name "MANUFACTURER PART NUMBER") "RC0402FR-07100RL")
        (field (name "MANUFACTURER") "YAGEO")
        (field (name "TOLERANCE") "1%")
      )
      (libsource (lib "database") (part "__template_resistor"))
    )
    (comp (ref "R66")
      (value "30")
      (footprint "R2512")
      (fields
        (field (name "MANUFACTURER PART NUMBER") "RC2512FK-0730RL")
        (field (name "MANUFACTURER") "YAGEO")
        (field (name "TOLERANCE") "1%")
      )
      (libsource (lib "database") (part "__template_resistor"))
    )
    (comp (ref "R67")
      (value "30")
      (footprint "R0402")
      (fields
        (field (name "MANUFACTURER PART NUMBER") "RC0402FR-0730RL")
        (field (name "MANUFACTURER") "YAGEO")
        (field (name "TOLERANCE") "1%")
      )
      (libsource (lib "database") (part "__template_resistor"))
    )
    (comp (ref "R68")
      (value "30")
      (footprint "R2512")
      (fields
        (field (name "MANUFACTURER PART NUMBER") "RC2512FK-0730RL")
        (field (name "MANUFACTURER") "YAGEO")
        (field (name "TOLERANCE") "1%")
      )
      (libsource (lib "database") (part "__template_resistor"))
    )
    (comp (ref "R69")
      (value "100")
      (footprint "R0402")
      (fields
        (field (name "MANUFACTURER PART NUMBER") "RC0402FR-07100RL")
        (field (name "MANUFACTURER") "YAGEO")
        (field (name "TOLERANCE") "1%")
      )
      (libsource (lib "database") (part "__template_resistor"))
    )
    (comp (ref "R70")
      (value "1k")
      (footprint "R0402")
      (fields
        (field (name "TOLERANCE") "1%")
        (field (name "MANUFACTURER PART NUMBER") "0402WGF1001TCE")
        (field (name "MANUFACTURER") "UNI-ROYAL(Uniroyal Elec)")
      )
      (libsource (lib "database") (part "__template_resistor"))
    )
    (comp (ref "R71")
      (value "30")
      (footprint "R2512")
      (fields
        (field (name "MANUFACTURER PART NUMBER") "RC2512FK-0730RL")
        (field (name "MANUFACTURER") "YAGEO")
        (field (name "TOLERANCE") "1%")
      )
      (libsource (lib "database") (part "__template_resistor"))
    )
    (comp (ref "R72")
      (value "30")
      (footprint "R2512")
      (fields
        (field (name "MANUFACTURER PART NUMBER") "RC2512FK-0730RL")
        (field (name "MANUFACTURER") "YAGEO")
        (field (name "TOLERANCE") "1%")
      )
      (libsource (lib "database") (part "__template_resistor"))
    )
    (comp (ref "R73")
      (value "100")
      (footprint "R0402")
      (fields
        (field (name "MANUFACTURER PART NUMBER") "RC0402FR-07100RL")
        (field (name "MANUFACTURER") "YAGEO")
        (field (name "TOLERANCE") "1%")
      )
      (libsource (lib "database") (part "__template_resistor"))
    )
    (comp (ref "R74")
      (value "1k")
      (footprint "R0402")
      (fields
        (field (name "TOLERANCE") "1%")
        (field (name "MANUFACTURER PART NUMBER") "0402WGF1001TCE")
        (field (name "MANUFACTURER") "UNI-ROYAL(Uniroyal Elec)")
      )
      (libsource (lib "database") (part "__template_resistor"))
    )
    (comp (ref "R75")
      (value "30")
      (footprint "R2512")
      (fields
        (field (name "MANUFACTURER PART NUMBER") "RC2512FK-0730RL")
        (field (name "MANUFACTURER") "YAGEO")
        (field (name "TOLERANCE") "1%")
      )
      (libsource (lib "database") (part "__template_resistor"))
    )
    (comp (ref "R76")
      (value "30")
      (footprint "R2512")
      (fields
        (field (name "MANUFACTURER PART NUMBER") "RC2512FK-0730RL")
        (field (name "MANUFACTURER") "YAGEO")
        (field (name "TOLERANCE") "1%")
      )
      (libsource (lib "database") (part "__template_resistor"))
    )
    (comp (ref "R77")
      (value "100")
      (footprint "R0402")
      (fields
        (field (name "MANUFACTURER PART NUMBER") "RC0402FR-07100RL")
        (field (name "MANUFACTURER") "YAGEO")
        (field (name "TOLERANCE") "1%")
      )
      (libsource (lib "database") (part "__template_resistor"))
    )
    (comp (ref "R78")
      (value "30")
      (footprint "R2512")
      (fields
        (field (name "MANUFACTURER PART NUMBER") "RC2512FK-0730RL")
        (field (name "MANUFACTURER") "YAGEO")
        (field (name "TOLERANCE") "1%")
      )
      (libsource (lib "database") (part "__template_resistor"))
    )
    (comp (ref "R79")
      (value "30")
      (footprint "R2512")
      (fields
        (field (name "MANUFACTURER PART NUMBER") "RC2512FK-0730RL")
        (field (name "MANUFACTURER") "YAGEO")
        (field (name "TOLERANCE") "1%")
      )
      (libsource (lib "database") (part "__template_resistor"))
    )
    (comp (ref "U1")
      (value "BQ79616PAPRQ1")
      (footprint "TI_PAP0064F")
      (description "IC MONITOR BATT STACK")
      (fields (field (name "MANUFACTURER") "Texas Instruments"))
      (libsource (lib "database") (part "BQ79616PAPRQ1"))
    )
  )
  (nets
    (net (code "3") (name "/AVDD") (class "Default")
      (node (ref "C40") (pin "1") (pintype "passive"))
      (node (ref "U1") (pin "38") (pinfunction "AVDD_38") (pintype "passive"))
    )
    (net (code "4") (name "/BAT") (class "Default")
      (node (ref "C29") (pin "2") (pintype "passive"))
      (node (ref "C32") (pin "1") (pintype "passive"))
      (node (ref "R67") (pin "2") (pintype "passive"))
      (node (ref "U1") (pin "1") (pinfunction "BAT_1") (pintype "passive"))
    )
    (net (code "5") (name "/CB0") (class "Default")
      (node (ref "C38") (pin "2") (pintype "passive"))
      (node (ref "C44") (pin "1") (pintype "passive"))
      (node (ref "R78") (pin "1") (pintype "passive"))
      (node (ref "R79") (pin "2") (pintype "passive"))
      (node (ref "U1") (pin "34") (pinfunction "CB0_34") (pintype "passive"))
    )
    (net (code "6") (name "/CB1") (class "Default")
      (node (ref "C35") (pin "2") (pintype "passive"))
      (node (ref "C38") (pin "1") (pintype "passive"))
      (node (ref "D16") (pin "2") (pintype "passive"))
      (node (ref "R75") (pin "1") (pintype "passive"))
      (node (ref "R76") (pin "2") (pintype "passive"))
      (node (ref "U1") (pin "32") (pinfunction "CB1_32") (pintype "passive"))
    )
    (net (code "7") (name "/CB2") (class "Default")
      (node (ref "C30") (pin "2") (pintype "passive"))
      (node (ref "C35") (pin "1") (pintype "passive"))
      (node (ref "D15") (pin "2") (pintype "passive"))
      (node (ref "R71") (pin "1") (pintype "passive"))
      (node (ref "R72") (pin "2") (pintype "passive"))
      (node (ref "U1") (pin "30") (pinfunction "CB2_30") (pintype "passive"))
    )
    (net (code "8") (name "/CB3") (class "Default")
      (node (ref "C27") (pin "2") (pintype "passive"))
      (node (ref "C30") (pin "1") (pintype "passive"))
      (node (ref "D14") (pin "2") (pintype "passive"))
      (node (ref "R66") (pin "1") (pintype "passive"))
      (node (ref "R68") (pin "2") (pintype "passive"))
      (node (ref "U1") (pin "28") (pinfunction "CB3_28") (pintype "passive"))
    )
    (net (code "9") (name "/CB4") (class "Default")
      (node (ref "C25") (pin "2") (pintype "passive"))
      (node (ref "C27") (pin "1") (pintype "passive"))
      (node (ref "D13") (pin "2") (pintype "passive"))
      (node (ref "R59") (pin "1") (pintype "passive"))
      (node (ref "R60") (pin "2") (pintype "passive"))
      (node (ref "U1") (pin "26") (pinfunction "CB4_26") (pintype "passive"))
    )
    (net (code "10") (name "/CB5") (class "Default")
      (node (ref "C23") (pin "2") (pintype "passive"))
      (node (ref "C25") (pin "1") (pintype "passive"))
      (node (ref "D12") (pin "2") (pintype "passive"))
      (node (ref "R55") (pin "1") (pintype "passive"))
      (node (ref "R56") (pin "2") (pintype "passive"))
      (node (ref "U1") (pin "24") (pinfunction "CB5_24") (pintype "passive"))
    )
    (net (code "11") (name "/CB6") (class "Default")
      (node (ref "C21") (pin "2") (pintype "passive"))
      (node (ref "C23") (pin "1") (pintype "passive"))
      (node (ref "D11") (pin "2") (pintype "passive"))
      (node (ref "R51") (pin "1") (pintype "passive"))
      (node (ref "R52") (pin "2") (pintype "passive"))
      (node (ref "U1") (pin "22") (pinfunction "CB6_22") (pintype "passive"))
    )
    (net (code "12") (name "/CB7") (class "Default")
      (node (ref "C19") (pin "2") (pintype "passive"))
      (node (ref "C21") (pin "1") (pintype "passive"))
      (node (ref "D10") (pin "2") (pintype "passive"))
      (node (ref "R47") (pin "1") (pintype "passive"))
      (node (ref "R48") (pin "2") (pintype "passive"))
      (node (ref "U1") (pin "20") (pinfunction "CB7_20") (pintype "passive"))
    )
    (net (code "13") (name "/CB8") (class "Default")
      (node (ref "C16") (pin "2") (pintype "passive"))
      (node (ref "C19") (pin "1") (pintype "passive"))
      (node (ref "D9") (pin "2") (pintype "passive"))
      (node (ref "R39") (pin "1") (pintype "passive"))
      (node (ref "R44") (pin "2") (pintype "passive"))
      (node (ref "U1") (pin "18") (pinfunction "CB8_18") (pintype "passive"))
    )
    (net (code "14") (name "/CB9") (class "Default")
      (node (ref "C14") (pin "2") (pintype "passive"))
      (node (ref "C16") (pin "1") (pintype "passive"))
      (node (ref "D8") (pin "2") (pintype "passive"))
      (node (ref "R31") (pin "1") (pintype "passive"))
      (node (ref "R32") (pin "2") (pintype "passive"))
      (node (ref "U1") (pin "16") (pinfunction "CB9_16") (pintype "passive"))
    )
    (net (code "15") (name "/CB10") (class "Default")
      (node (ref "C12") (pin "2") (pintype "passive"))
      (node (ref "C14") (pin "1") (pintype "passive"))
      (node (ref "D7") (pin "2") (pintype "passive"))
      (node (ref "R27") (pin "1") (pintype "passive"))
      (node (ref "R28") (pin "2") (pintype "passive"))
      (node (ref "U1") (pin "14") (pinfunction "CB10_14") (pintype "passive"))
    )
    (net (code "16") (name "/CB11") (class "Default")
      (node (ref "C10") (pin "2") (pintype "passive"))
      (node (ref "C12") (pin "1") (pintype "passive"))
      (node (ref "D6") (pin "2") (pintype "passive"))
      (node (ref "R23") (pin "1") (pintype "passive"))
      (node (ref "R24") (pin "2") (pintype "passive"))
      (node (ref "U1") (pin "12") (pinfunction "CB11_12") (pintype "passive"))
    )
    (net (code "17") (name "/CB12") (class "Default")
      (node (ref "C10") (pin "1") (pintype "passive"))
      (node (ref "C8") (pin "2") (pintype "passive"))
      (node (ref "D5") (pin "2") (pintype "passive"))
      (node (ref "R19") (pin "1") (pintype "passive"))
      (node (ref "R20") (pin "2") (pintype "passive"))
      (node (ref "U1") (pin "10") (pinfunction "CB12_10") (pintype "passive"))
    )
    (net (code "18") (name "/CB13") (class "Default")
      (node (ref "C6") (pin "2") (pintype "passive"))
      (node (ref "C8") (pin "1") (pintype "passive"))
      (node (ref "D4") (pin "2") (pintype "passive"))
      (node (ref "R15") (pin "1") (pintype "passive"))
      (node (ref "R16") (pin "2") (pintype "passive"))
      (node (ref "U1") (pin "8") (pinfunction "CB13_8") (pintype "passive"))
    )
    (net (code "19") (name "/CB14") (class "Default")
      (node (ref "C4") (pin "2") (pintype "passive"))
      (node (ref "C6") (pin "1") (pintype "passive"))
      (node (ref "D3") (pin "2") (pintype "passive"))
      (node (ref "R11") (pin "1") (pintype "passive"))
      (node (ref "R12") (pin "2") (pintype "passive"))
      (node (ref "U1") (pin "6") (pinfunction "CB14_6") (pintype "passive"))
    )
    (net (code "20") (name "/CB15") (class "Default")
      (node (ref "C2") (pin "2") (pintype "passive"))
      (node (ref "C4") (pin "1") (pintype "passive"))
      (node (ref "D2") (pin "2") (pintype "passive"))
      (node (ref "R7") (pin "1") (pintype "passive"))
      (node (ref "R8") (pin "2") (pintype "passive"))
      (node (ref "U1") (pin "4") (pinfunction "CB15_4") (pintype "passive"))
    )
    (net (code "21") (name "/CB16") (class "Default")
      (node (ref "C2") (pin "1") (pintype "passive"))
      (node (ref "C29") (pin "1") (pintype "passive"))
      (node (ref "D1") (pin "2") (pintype "passive"))
      (node (ref "R3") (pin "1") (pintype "passive"))
      (node (ref "R4") (pin "2") (pintype "passive"))
      (node (ref "U1") (pin "2") (pinfunction "CB16_2") (pintype "passive"))
    )
    (net (code "22") (name "/CELL0") (class "Default")
      (node (ref "F18") (pin "1") (pintype "passive"))
      (node (ref "F19") (pin "1") (pintype "passive"))
      (node (ref "MH32") (pin "1") (pintype "passive"))
    )
    (net (code "23") (name "/CELL1") (class "Default")
      (node (ref "F17") (pin "1") (pintype "passive"))
      (node (ref "MH30") (pin "1") (pintype "passive"))
      (node (ref "MH31") (pin "1") (pintype "passive"))
    )
    (net (code "24") (name "/CELL2") (class "Default")
      (node (ref "F16") (pin "1") (pintype "passive"))
      (node (ref "MH28") (pin "1") (pintype "passive"))
      (node (ref "MH29") (pin "1") (pintype "passive"))
    )
    (net (code "25") (name "/CELL3") (class "Default")
      (node (ref "F15") (pin "1") (pintype "passive"))
      (node (ref "MH26") (pin "1") (pintype "passive"))
      (node (ref "MH27") (pin "1") (pintype "passive"))
    )
    (net (code "26") (name "/CELL4") (class "Default")
      (node (ref "F14") (pin "1") (pintype "passive"))
      (node (ref "MH24") (pin "1") (pintype "passive"))
      (node (ref "MH25") (pin "1") (pintype "passive"))
    )
    (net (code "27") (name "/CELL5") (class "Default")
      (node (ref "F13") (pin "1") (pintype "passive"))
      (node (ref "MH22") (pin "1") (pintype "passive"))
      (node (ref "MH23") (pin "1") (pintype "passive"))
    )
    (net (code "28") (name "/CELL6") (class "Default")
      (node (ref "F12") (pin "1") (pintype "passive"))
      (node (ref "MH20") (pin "1") (pintype "passive"))
      (node (ref "MH21") (pin "1") (pintype "passive"))
    )
    (net (code "29") (name "/CELL7") (class "Default")
      (node (ref "F11") (pin "1") (pintype "passive"))
      (node (ref "MH18") (pin "1") (pintype "passive"))
      (node (ref "MH19") (pin "1") (pintype "passive"))
    )
    (net (code "30") (name "/CELL8") (class "Default")
      (node (ref "F10") (pin "1") (pintype "passive"))
      (node (ref "MH16") (pin "1") (pintype "passive"))
      (node (ref "MH17") (pin "1") (pintype "passive"))
    )
    (net (code "31") (name "/CELL9") (class "Default")
      (node (ref "F9") (pin "1") (pintype "passive"))
      (node (ref "MH14") (pin "1") (pintype "passive"))
      (node (ref "MH15") (pin "1") (pintype "passive"))
    )
    (net (code "32") (name "/CELL10") (class "Default")
      (node (ref "F8") (pin "1") (pintype "passive"))
      (node (ref "MH12") (pin "1") (pintype "passive"))
      (node (ref "MH13") (pin "1") (pintype "passive"))
    )
    (net (code "33") (name "/CELL11") (class "Default")
      (node (ref "F7") (pin "1") (pintype "passive"))
      (node (ref "MH10") (pin "1") (pintype "passive"))
      (node (ref "MH11") (pin "1") (pintype "passive"))
    )
    (net (code "34") (name "/CELL12") (class "Default")
      (node (ref "F6") (pin "1") (pintype "passive"))
      (node (ref "MH8") (pin "1") (pintype "passive"))
      (node (ref "MH9") (pin "1") (pintype "passive"))
    )
    (net (code "35") (name "/CELL13") (class "Default")
      (node (ref "F5") (pin "1") (pintype "passive"))
      (node (ref "MH6") (pin "1") (pintype "passive"))
      (node (ref "MH7") (pin "1") (pintype "passive"))
    )
    (net (code "36") (name "/CELL14") (class "Default")
      (node (ref "F4") (pin "1") (pintype "passive"))
      (node (ref "MH4") (pin "1") (pintype "passive"))
      (node (ref "MH5") (pin "1") (pintype "passive"))
    )
    (net (code "37") (name "/CELL15") (class "Default")
      (node (ref "F3") (pin "1") (pintype "passive"))
      (node (ref "MH2") (pin "1") (pintype "passive"))
      (node (ref "MH3") (pin "1") (pintype "passive"))
    )
    (net (code "38") (name "/CELL16") (class "Default")
      (node (ref "F1") (pin "1") (pintype "passive"))
      (node (ref "F2") (pin "1") (pintype "passive"))
      (node (ref "MH1") (pin "1") (pintype "passive"))
    )
    (net (code "41") (name "/CVDD") (class "Default")
      (node (ref "C43") (pin "1") (pintype "passive"))
      (node (ref "U1") (pin "45") (pinfunction "CVDD_45") (pintype "passive"))
      (node (ref "U1") (pin "52") (pinfunction "RX_52") (pintype "passive"))
    )
    (net (code "42") (name "/DVDD") (class "Default")
      (node (ref "C39") (pin "1") (pintype "passive"))
      (node (ref "U1") (pin "49") (pinfunction "DVDD_49") (pintype "passive"))
    )
    (net (code "43") (name "/FUSED0") (class "Default")
      (node (ref "F18") (pin "2") (pintype "passive"))
      (node (ref "R77") (pin "1") (pintype "passive"))
      (node (ref "R78") (pin "2") (pintype "passive"))
      (node (ref "R79") (pin "1") (pintype "passive"))
    )
    (net (code "44") (name "/FUSED1") (class "Default")
      (node (ref "F17") (pin "2") (pintype "passive"))
      (node (ref "R73") (pin "1") (pintype "passive"))
      (node (ref "R74") (pin "1") (pintype "passive"))
      (node (ref "R75") (pin "2") (pintype "passive"))
      (node (ref "R76") (pin "1") (pintype "passive"))
    )
    (net (code "45") (name "/FUSED2") (class "Default")
      (node (ref "F16") (pin "2") (pintype "passive"))
      (node (ref "R69") (pin "1") (pintype "passive"))
      (node (ref "R70") (pin "1") (pintype "passive"))
      (node (ref "R71") (pin "2") (pintype "passive"))
      (node (ref "R72") (pin "1") (pintype "passive"))
    )
    (net (code "46") (name "/FUSED3") (class "Default")
      (node (ref "F15") (pin "2") (pintype "passive"))
      (node (ref "R61") (pin "1") (pintype "passive"))
      (node (ref "R62") (pin "1") (pintype "passive"))
      (node (ref "R66") (pin "2") (pintype "passive"))
      (node (ref "R68") (pin "1") (pintype "passive"))
    )
    (net (code "47") (name "/FUSED4") (class "Default")
      (node (ref "F14") (pin "2") (pintype "passive"))
      (node (ref "R57") (pin "1") (pintype "passive"))
      (node (ref "R58") (pin "1") (pintype "passive"))
      (node (ref "R59") (pin "2") (pintype "passive"))
      (node (ref "R60") (pin "1") (pintype "passive"))
    )
    (net (code "48") (name "/FUSED5") (class "Default")
      (node (ref "F13") (pin "2") (pintype "passive"))
      (node (ref "R53") (pin "1") (pintype "passive"))
      (node (ref "R54") (pin "1") (pintype "passive"))
      (node (ref "R55") (pin "2") (pintype "passive"))
      (node (ref "R56") (pin "1") (pintype "passive"))
    )
    (net (code "49") (name "/FUSED6") (class "Default")
      (node (ref "F12") (pin "2") (pintype "passive"))
      (node (ref "R49") (pin "1") (pintype "passive"))
      (node (ref "R50") (pin "1") (pintype "passive"))
      (node (ref "R51") (pin "2") (pintype "passive"))
      (node (ref "R52") (pin "1") (pintype "passive"))
    )
    (net (code "50") (name "/FUSED7") (class "Default")
      (node (ref "F11") (pin "2") (pintype "passive"))
      (node (ref "R45") (pin "1") (pintype "passive"))
      (node (ref "R46") (pin "1") (pintype "passive"))
      (node (ref "R47") (pin "2") (pintype "passive"))
      (node (ref "R48") (pin "1") (pintype "passive"))
    )
    (net (code "51") (name "/FUSED8") (class "Default")
      (node (ref "F10") (pin "2") (pintype "passive"))
      (node (ref "R33") (pin "1") (pintype "passive"))
      (node (ref "R34") (pin "1") (pintype "passive"))
      (node (ref "R39") (pin "2") (pintype "passive"))
      (node (ref "R44") (pin "1") (pintype "passive"))
    )
    (net (code "52") (name "/FUSED9") (class "Default")
      (node (ref "F9") (pin "2") (pintype "passive"))
      (node (ref "R29") (pin "1") (pintype "passive"))
      (node (ref "R30") (pin "1") (pintype "passive"))
      (node (ref "R31") (pin "2") (pintype "passive"))
      (node (ref "R32") (pin "1") (pintype "passive"))
    )
    (net (code "53") (name "/FUSED10") (class "Default")
      (node (ref "F8") (pin "2") (pintype "passive"))
      (node (ref "R25") (pin "1") (pintype "passive"))
      (node (ref "R26") (pin "1") (pintype "passive"))
      (node (ref "R27") (pin "2") (pintype "passive"))
      (node (ref "R28") (pin "1") (pintype "passive"))
    )
    (net (code "54") (name "/FUSED11") (class "Default")
      (node (ref "F7") (pin "2") (pintype "passive"))
      (node (ref "R21") (pin "1") (pintype "passive"))
      (node (ref "R22") (pin "1") (pintype "passive"))
      (node (ref "R23") (pin "2") (pintype "passive"))
      (node (ref "R24") (pin "1") (pintype "passive"))
    )
    (net (code "55") (name "/FUSED12") (class "Default")
      (node (ref "F6") (pin "2") (pintype "passive"))
      (node (ref "R17") (pin "1") (pintype "passive"))
      (node (ref "R18") (pin "1") (pintype "passive"))
      (node (ref "R19") (pin "2") (pintype "passive"))
      (node (ref "R20") (pin "1") (pintype "passive"))
    )
    (net (code "56") (name "/FUSED13") (class "Default")
      (node (ref "F5") (pin "2") (pintype "passive"))
      (node (ref "R13") (pin "1") (pintype "passive"))
      (node (ref "R14") (pin "1") (pintype "passive"))
      (node (ref "R15") (pin "2") (pintype "passive"))
      (node (ref "R16") (pin "1") (pintype "passive"))
    )
    (net (code "57") (name "/FUSED14") (class "Default")
      (node (ref "F4") (pin "2") (pintype "passive"))
      (node (ref "R10") (pin "1") (pintype "passive"))
      (node (ref "R11") (pin "2") (pintype "passive"))
      (node (ref "R12") (pin "1") (pintype "passive"))
      (node (ref "R9") (pin "1") (pintype "passive"))
    )
    (net (code "58") (name "/FUSED15") (class "Default")
      (node (ref "F3") (pin "2") (pintype "passive"))
      (node (ref "R5") (pin "1") (pintype "passive"))
      (node (ref "R6") (pin "1") (pintype "passive"))
      (node (ref "R7") (pin "2") (pintype "passive"))
      (node (ref "R8") (pin "1") (pintype "passive"))
    )
    (net (code "59") (name "/FUSED16") (class "Default")
      (node (ref "F2") (pin "2") (pintype "passive"))
      (node (ref "R1") (pin "1") (pintype "passive"))
      (node (ref "R2") (pin "1") (pintype "passive"))
      (node (ref "R3") (pin "2") (pintype "passive"))
      (node (ref "R4") (pin "1") (pintype "passive"))
    )
    (net (code "60") (name "/GPIO1") (class "Default")
      (node (ref "J1") (pin "3") (pintype "passive"))
      (node (ref "J1") (pin "4") (pintype "passive"))
      (node (ref "R35") (pin "2") (pintype "passive"))
      (node (ref "U1") (pin "61") (pinfunction "GPIO1_61") (pintype "passive"))
    )
    (net (code "61") (name "/GPIO2") (class "Default")
      (node (ref "J2") (pin "3") (pintype "passive"))
      (node (ref "J2") (pin "4") (pintype "passive"))
      (node (ref "R40") (pin "2") (pintype "passive"))
      (node (ref "U1") (pin "60") (pinfunction "GPIO2_60") (pintype "passive"))
    )
    (net (code "62") (name "/GPIO3") (class "Default")
      (node (ref "J3") (pin "3") (pintype "passive"))
      (node (ref "J3") (pin "4") (pintype "passive"))
      (node (ref "R36") (pin "2") (pintype "passive"))
      (node (ref "U1") (pin "59") (pinfunction "GPIO3_59") (pintype "passive"))
    )
    (net (code "63") (name "/GPIO4") (class "Default")
      (node (ref "J4") (pin "3") (pintype "passive"))
      (node (ref "J4") (pin "4") (pintype "passive"))
      (node (ref "R41") (pin "2") (pintype "passive"))
      (node (ref "U1") (pin "58") (pinfunction "GPIO4_58") (pintype "passive"))
    )
    (net (code "64") (name "/GPIO5") (class "Default")
      (node (ref "J5") (pin "3") (pintype "passive"))
      (node (ref "J5") (pin "4") (pintype "passive"))
      (node (ref "R37") (pin "2") (pintype "passive"))
      (node (ref "U1") (pin "57") (pinfunction "GPIO5_57") (pintype "passive"))
    )
    (net (code "65") (name "/GPIO6") (class "Default")
      (node (ref "J6") (pin "3") (pintype "passive"))
      (node (ref "J6") (pin "4") (pintype "passive"))
      (node (ref "R42") (pin "2") (pintype "passive"))
      (node (ref "U1") (pin "56") (pinfunction "GPIO6_56") (pintype "passive"))
    )
    (net (code "66") (name "/GPIO7") (class "Default")
      (node (ref "J7") (pin "3") (pintype "passive"))
      (node (ref "J7") (pin "4") (pintype "passive"))
      (node (ref "R38") (pin "2") (pintype "passive"))
      (node (ref "U1") (pin "55") (pinfunction "GPIO7_55") (pintype "passive"))
    )
    (net (code "67") (name "/GPIO8") (class "Default")
      (node (ref "J8") (pin "3") (pintype "passive"))
      (node (ref "J8") (pin "4") (pintype "passive"))
      (node (ref "R43") (pin "2") (pintype "passive"))
      (node (ref "U1") (pin "54") (pinfunction "GPIO8_54") (pintype "passive"))
    )
    (net (code "68") (name "/LDOIN") (class "Default")
      (node (ref "C34") (pin "1") (pintype "passive"))
      (node (ref "Q1") (pin "3") (pinfunction "E_3") (pintype "passive"))
      (node (ref "U1") (pin "47") (pinfunction "LDOIN_47") (pintype "passive"))
    )
    (net (code "69") (name "/NEG5V") (class "Default")
      (node (ref "C41") (pin "1") (pintype "passive"))
      (node (ref "U1") (pin "44") (pinfunction "NEG5V_44") (pintype "passive"))
    )
    (net (code "70") (name "/NPNB") (class "Default")
      (node (ref "Q1") (pin "1") (pinfunction "B_1") (pintype "passive"))
      (node (ref "U1") (pin "48") (pinfunction "NPNB_48") (pintype "passive"))
    )
    (net (code "71") (name "/NPNC") (class "Default")
      (node (ref "C31") (pin "1") (pintype "passive"))
      (node (ref "Q1") (pin "2") (pinfunction "C_2") (pintype "passive"))
      (node (ref "Q1") (pin "4") (pinfunction "C_4") (pintype "passive"))
      (node (ref "R65") (pin "1") (pintype "passive"))
    )
    (net (code "72") (name "/REFHP") (class "Default")
      (node (ref "C36") (pin "1") (pintype "passive"))
      (node (ref "U1") (pin "37") (pinfunction "REFHP_37") (pintype "passive"))
    )
    (net (code "73") (name "/TSREF") (class "Default")
      (node (ref "C18") (pin "1") (pintype "passive"))
      (node (ref "R35") (pin "1") (pintype "passive"))
      (node (ref "R36") (pin "1") (pintype "passive"))
      (node (ref "R37") (pin "1") (pintype "passive"))
      (node (ref "R38") (pin "1") (pintype "passive"))
      (node (ref "R40") (pin "1") (pintype "passive"))
      (node (ref "R41") (pin "1") (pintype "passive"))
      (node (ref "R42") (pin "1") (pintype "passive"))
      (node (ref "R43") (pin "1") (pintype "passive"))
      (node (ref "U1") (pin "51") (pinfunction "TSREF_51") (pintype "passive"))
    )
    (net (code "74") (name "/VC0") (class "Default")
      (node (ref "C37") (pin "2") (pintype "passive"))
      (node (ref "C42") (pin "1") (pintype "passive"))
      (node (ref "R77") (pin "2") (pintype "passive"))
      (node (ref "U1") (pin "35") (pinfunction "VC0_35") (pintype "passive"))
    )
    (net (code "75") (name "/VC1") (class "Default")
      (node (ref "C33") (pin "2") (pintype "passive"))
      (node (ref "C37") (pin "1") (pintype "passive"))
      (node (ref "R73") (pin "2") (pintype "passive"))
      (node (ref "U1") (pin "33") (pinfunction "VC1_33") (pintype "passive"))
    )
    (net (code "76") (name "/VC2") (class "Default")
      (node (ref "C28") (pin "2") (pintype "passive"))
      (node (ref "C33") (pin "1") (pintype "passive"))
      (node (ref "R69") (pin "2") (pintype "passive"))
      (node (ref "U1") (pin "31") (pinfunction "VC2_31") (pintype "passive"))
    )
    (net (code "77") (name "/VC3") (class "Default")
      (node (ref "C26") (pin "2") (pintype "passive"))
      (node (ref "C28") (pin "1") (pintype "passive"))
      (node (ref "R61") (pin "2") (pintype "passive"))
      (node (ref "U1") (pin "29") (pinfunction "VC3_29") (pintype "passive"))
    )
    (net (code "78") (name "/VC4") (class "Default")
      (node (ref "C24") (pin "2") (pintype "passive"))
      (node (ref "C26") (pin "1") (pintype "passive"))
      (node (ref "R57") (pin "2") (pintype "passive"))
      (node (ref "U1") (pin "27") (pinfunction "VC4_27") (pintype "passive"))
    )
    (net (code "79") (name "/VC5") (class "Default")
      (node (ref "C22") (pin "2") (pintype "passive"))
      (node (ref "C24") (pin "1") (pintype "passive"))
      (node (ref "R53") (pin "2") (pintype "passive"))
      (node (ref "U1") (pin "25") (pinfunction "VC5_25") (pintype "passive"))
    )
    (net (code "80") (name "/VC6") (class "Default")
      (node (ref "C20") (pin "2") (pintype "passive"))
      (node (ref "C22") (pin "1") (pintype "passive"))
      (node (ref "R49") (pin "2") (pintype "passive"))
      (node (ref "U1") (pin "23") (pinfunction "VC6_23") (pintype "passive"))
    )
    (net (code "81") (name "/VC7") (class "Default")
      (node (ref "C17") (pin "2") (pintype "passive"))
      (node (ref "C20") (pin "1") (pintype "passive"))
      (node (ref "R45") (pin "2") (pintype "passive"))
      (node (ref "U1") (pin "21") (pinfunction "VC7_21") (pintype "passive"))
    )
    (net (code "82") (name "/VC8") (class "Default")
      (node (ref "C15") (pin "2") (pintype "passive"))
      (node (ref "C17") (pin "1") (pintype "passive"))
      (node (ref "R33") (pin "2") (pintype "passive"))
      (node (ref "U1") (pin "19") (pinfunction "VC8_19") (pintype "passive"))
    )
    (net (code "83") (name "/VC9") (class "Default")
      (node (ref "C13") (pin "2") (pintype "passive"))
      (node (ref "C15") (pin "1") (pintype "passive"))
      (node (ref "R29") (pin "2") (pintype "passive"))
      (node (ref "U1") (pin "17") (pinfunction "VC9_17") (pintype "passive"))
    )
    (net (code "84") (name "/VC10") (class "Default")
      (node (ref "C11") (pin "2") (pintype "passive"))
      (node (ref "C13") (pin "1") (pintype "passive"))
      (node (ref "R25") (pin "2") (pintype "passive"))
      (node (ref "U1") (pin "15") (pinfunction "VC10_15") (pintype "passive"))
    )
    (net (code "85") (name "/VC11") (class "Default")
      (node (ref "C11") (pin "1") (pintype "passive"))
      (node (ref "C9") (pin "2") (pintype "passive"))
      (node (ref "R21") (pin "2") (pintype "passive"))
      (node (ref "U1") (pin "13") (pinfunction "VC11_13") (pintype "passive"))
    )
    (net (code "86") (name "/VC12") (class "Default")
      (node (ref "C7") (pin "2") (pintype "passive"))
      (node (ref "C9") (pin "1") (pintype "passive"))
      (node (ref "R17") (pin "2") (pintype "passive"))
      (node (ref "U1") (pin "11") (pinfunction "VC12_11") (pintype "passive"))
    )
    (net (code "87") (name "/VC13") (class "Default")
      (node (ref "C5") (pin "2") (pintype "passive"))
      (node (ref "C7") (pin "1") (pintype "passive"))
      (node (ref "R13") (pin "2") (pintype "passive"))
      (node (ref "U1") (pin "9") (pinfunction "VC13_9") (pintype "passive"))
    )
    (net (code "88") (name "/VC14") (class "Default")
      (node (ref "C3") (pin "2") (pintype "passive"))
      (node (ref "C5") (pin "1") (pintype "passive"))
      (node (ref "R9") (pin "2") (pintype "passive"))
      (node (ref "U1") (pin "7") (pinfunction "VC14_7") (pintype "passive"))
    )
    (net (code "89") (name "/VC15") (class "Default")
      (node (ref "C1") (pin "2") (pintype "passive"))
      (node (ref "C3") (pin "1") (pintype "passive"))
      (node (ref "R5") (pin "2") (pintype "passive"))
      (node (ref "U1") (pin "5") (pinfunction "VC15_5") (pintype "passive"))
    )
    (net (code "90") (name "/VC16") (class "Default")
      (node (ref "C1") (pin "1") (pintype "passive"))
      (node (ref "R1") (pin "2") (pintype "passive"))
      (node (ref "U1") (pin "3") (pinfunction "VC16_3") (pintype "passive"))
    )
    (net (code "91") (name "GND") (class "Default")
      (node (ref "C18") (pin "2") (pintype "passive"))
      (node (ref "C31") (pin "2") (pintype "passive"))
      (node (ref "C32") (pin "2") (pintype "passive"))
      (node (ref "C34") (pin "2") (pintype "passive"))
      (node (ref "C36") (pin "2") (pintype "passive"))
      (node (ref "C39") (pin "2") (pintype "passive"))
      (node (ref "C40") (pin "2") (pintype "passive"))
      (node (ref "C41") (pin "2") (pintype "passive"))
      (node (ref "C42") (pin "2") (pintype "passive"))
      (node (ref "C43") (pin "2") (pintype "passive"))
      (node (ref "C44") (pin "2") (pintype "passive"))
      (node (ref "F19") (pin "2") (pintype "passive"))
      (node (ref "J1") (pin "1") (pintype "passive"))
      (node (ref "J1") (pin "2") (pintype "passive"))
      (node (ref "J2") (pin "1") (pintype "passive"))
      (node (ref "J2") (pin "2") (pintype "passive"))
      (node (ref "J3") (pin "1") (pintype "passive"))
      (node (ref "J3") (pin "2") (pintype "passive"))
      (node (ref "J4") (pin "1") (pintype "passive"))
      (node (ref "J4") (pin "2") (pintype "passive"))
      (node (ref "J5") (pin "1") (pintype "passive"))
      (node (ref "J5") (pin "2") (pintype "passive"))
      (node (ref "J6") (pin "1") (pintype "passive"))
      (node (ref "J6") (pin "2") (pintype "passive"))
      (node (ref "J7") (pin "1") (pintype "passive"))
      (node (ref "J7") (pin "2") (pintype "passive"))
      (node (ref "J8") (pin "1") (pintype "passive"))
      (node (ref "J8") (pin "2") (pintype "passive"))
      (node (ref "U1") (pin "36") (pinfunction "REFHM_36") (pintype "passive"))
      (node (ref "U1") (pin "39") (pinfunction "AVSS_39") (pintype "passive"))
      (node (ref "U1") (pin "46") (pinfunction "CVSS_46") (pintype "passive"))
      (node (ref "U1") (pin "50") (pinfunction "DVSS_50") (pintype "passive"))
      (node (ref "U1") (pin "EP0") (pinfunction "PAD_EP0") (pintype "passive"))
    )
    (net (code "92") (name "Net-(D1-Pad1)") (class "Default")
      (node (ref "D1") (pin "1") (pintype "passive"))
      (node (ref "R2") (pin "2") (pintype "passive"))
    )
    (net (code "93") (name "Net-(D2-Pad1)") (class "Default")
      (node (ref "D2") (pin "1") (pintype "passive"))
      (node (ref "R6") (pin "2") (pintype "passive"))
    )
    (net (code "94") (name "Net-(D3-Pad1)") (class "Default")
      (node (ref "D3") (pin "1") (pintype "passive"))
      (node (ref "R10") (pin "2") (pintype "passive"))
    )
    (net (code "95") (name "Net-(D4-Pad1)") (class "Default")
      (node (ref "D4") (pin "1") (pintype "passive"))
      (node (ref "R14") (pin "2") (pintype "passive"))
    )
    (net (code "96") (name "Net-(D5-Pad1)") (class "Default")
      (node (ref "D5") (pin "1") (pintype "passive"))
      (node (ref "R18") (pin "2") (pintype "passive"))
    )
    (net (code "97") (name "Net-(D6-Pad1)") (class "Default")
      (node (ref "D6") (pin "1") (pintype "passive"))
      (node (ref "R22") (pin "2") (pintype "passive"))
    )
    (net (code "98") (name "Net-(D7-Pad1)") (class "Default")
      (node (ref "D7") (pin "1") (pintype "passive"))
      (node (ref "R26") (pin "2") (pintype "passive"))
    )
    (net (code "99") (name "Net-(D8-Pad1)") (class "Default")
      (node (ref "D8") (pin "1") (pintype "passive"))
      (node (ref "R30") (pin "2") (pintype "passive"))
    )
    (net (code "100") (name "Net-(D9-Pad1)") (class "Default")
      (node (ref "D9") (pin "1") (pintype "passive"))
      (node (ref "R34") (pin "2") (pintype "passive"))
    )
    (net (code "101") (name "Net-(D10-Pad1)") (class "Default")
      (node (ref "D10") (pin "1") (pintype "passive"))
      (node (ref "R46") (pin "2") (pintype "passive"))
    )
    (net (code "102") (name "Net-(D11-Pad1)") (class "Default")
      (node (ref "D11") (pin "1") (pintype "passive"))
      (node (ref "R50") (pin "2") (pintype "passive"))
    )
    (net (code "103") (name "Net-(D12-Pad1)") (class "Default")
      (node (ref "D12") (pin "1") (pintype "passive"))
      (node (ref "R54") (pin "2") (pintype "passive"))
    )
    (net (code "104") (name "Net-(D13-Pad1)") (class "Default")
      (node (ref "D13") (pin "1") (pintype "passive"))
      (node (ref "R58") (pin "2") (pintype "passive"))
    )
    (net (code "105") (name "Net-(D14-Pad1)") (class "Default")
      (node (ref "D14") (pin "1") (pintype "passive"))
      (node (ref "R62") (pin "2") (pintype "passive"))
    )
    (net (code "106") (name "Net-(D15-Pad1)") (class "Default")
      (node (ref "D15") (pin "1") (pintype "passive"))
      (node (ref "R70") (pin "2") (pintype "passive"))
    )
    (net (code "107") (name "Net-(D16-Pad1)") (class "Default")
      (node (ref "D16") (pin "1") (pintype "passive"))
      (node (ref "R74") (pin "2") (pintype "passive"))
    )
    (net (code "108") (name "Net-(F1-Pad2)") (class "Default")
      (node (ref "F1") (pin "2") (pintype "passive"))
      (node (ref "R63") (pin "2") (pintype "passive"))
      (node (ref "R67") (pin "1") (pintype "passive"))
    )
    (net (code "109") (name "Net-(R63-Pad1)") (class "Default")
      (node (ref "R63") (pin "1") (pintype "passive"))
      (node (ref "R64") (pin "2") (pintype "passive"))
    )
    (net (code "110") (name "Net-(R64-Pad1)") (class "Default")
      (node (ref "R64") (pin "1") (pintype "passive"))
      (node (ref "R65") (pin "2") (pintype "passive"))
    )
    (net (code "111") (name "unconnected-(J1-TAB-PadEP0)") (class "Default")
      (node (ref "J1") (pin "EP0") (pinfunction "TAB_EP0") (pintype "passive"))
    )
    (net (code "112") (name "unconnected-(J1-TAB-PadEP1)") (class "Default")
      (node (ref "J1") (pin "EP1") (pinfunction "TAB_EP1") (pintype "passive"))
    )
    (net (code "113") (name "unconnected-(J2-TAB-PadEP0)") (class "Default")
      (node (ref "J2") (pin "EP0") (pinfunction "TAB_EP0") (pintype "passive"))
    )
    (net (code "114") (name "unconnected-(J2-TAB-PadEP1)") (class "Default")
      (node (ref "J2") (pin "EP1") (pinfunction "TAB_EP1") (pintype "passive"))
    )
    (net (code "115") (name "unconnected-(J3-TAB-PadEP0)") (class "Default")
      (node (ref "J3") (pin "EP0") (pinfunction "TAB_EP0") (pintype "passive"))
    )
    (net (code "116") (name "unconnected-(J3-TAB-PadEP1)") (class "Default")
      (node (ref "J3") (pin "EP1") (pinfunction "TAB_EP1") (pintype "passive"))
    )
    (net (code "117") (name "unconnected-(J4-TAB-PadEP0)") (class "Default")
      (node (ref "J4") (pin "EP0") (pinfunction "TAB_EP0") (pintype "passive"))
    )
    (net (code "118") (name "unconnected-(J4-TAB-PadEP1)") (class "Default")
      (node (ref "J4") (pin "EP1") (pinfunction "TAB_EP1") (pintype "passive"))
    )
    (net (code "119") (name "unconnected-(J5-TAB-PadEP0)") (class "Default")
      (node (ref "J5") (pin "EP0") (pinfunction "TAB_EP0") (pintype "passive"))
    )
    (net (code "120") (name "unconnected-(J5-TAB-PadEP1)") (class "Default")
      (node (ref "J5") (pin "EP1") (pinfunction "TAB_EP1") (pintype "passive"))
    )
    (net (code "121") (name "unconnected-(J6-TAB-PadEP0)") (class "Default")
      (node (ref "J6") (pin "EP0") (pinfunction "TAB_EP0") (pintype "passive"))
    )
    (net (code "122") (name "unconnected-(J6-TAB-PadEP1)") (class "Default")
      (node (ref "J6") (pin "EP1") (pinfunction "TAB_EP1") (pintype "passive"))
    )
    (net (code "123") (name "unconnected-(J7-TAB-PadEP0)") (class "Default")
      (node (ref "J7") (pin "EP0") (pinfunction "TAB_EP0") (pintype "passive"))
    )
    (net (code "124") (name "unconnected-(J7-TAB-PadEP1)") (class "Default")
      (node (ref "J7") (pin "EP1") (pinfunction "TAB_EP1") (pintype "passive"))
    )
    (net (code "125") (name "unconnected-(J8-TAB-PadEP0)") (class "Default")
      (node (ref "J8") (pin "EP0") (pinfunction "TAB_EP0") (pintype "passive"))
    )
    (net (code "126") (name "unconnected-(J8-TAB-PadEP1)") (class "Default")
      (node (ref "J8") (pin "EP1") (pinfunction "TAB_EP1") (pintype "passive"))
    )
    (net (code "127") (name "unconnected-(U1B-BBN-Pad63)") (class "Default")
      (node (ref "U1") (pin "63") (pinfunction "BBN_63") (pintype "passive"))
    )
    (net (code "128") (name "unconnected-(U1B-BBP-Pad64)") (class "Default")
      (node (ref "U1") (pin "64") (pinfunction "BBP_64") (pintype "passive"))
    )
    (net (code "129") (name "unconnected-(U1B-nFAULT-Pad62)") (class "Default")
      (node (ref "U1") (pin "62") (pinfunction "nFAULT_62") (pintype "passive"))
    )
    (net (code "130") (name "unconnected-(U1C-COMHN-Pad42)") (class "Default")
      (node (ref "U1") (pin "42") (pinfunction "COMHN_42") (pintype "passive"))
    )
    (net (code "131") (name "unconnected-(U1C-COMHP-Pad43)") (class "Default")
      (node (ref "U1") (pin "43") (pinfunction "COMHP_43") (pintype "passive"))
    )
    (net (code "132") (name "unconnected-(U1C-COMLN-Pad41)") (class "Default")
      (node (ref "U1") (pin "41") (pinfunction "COMLN_41") (pintype "passive"))
    )
    (net (code "133") (name "unconnected-(U1C-COMLP-Pad40)") (class "Default")
      (node (ref "U1") (pin "40") (pinfunction "COMLP_40") (pintype "passive"))
    )
    (net (code "134") (name "unconnected-(U1C-TX-Pad53)") (class "Default")
      (node (ref "U1") (pin "53") (pinfunction "TX_53") (pintype "passive"))
    )
  )
)
